# Module.net
KiCad netlist of a schematic drawn in Altium Designer
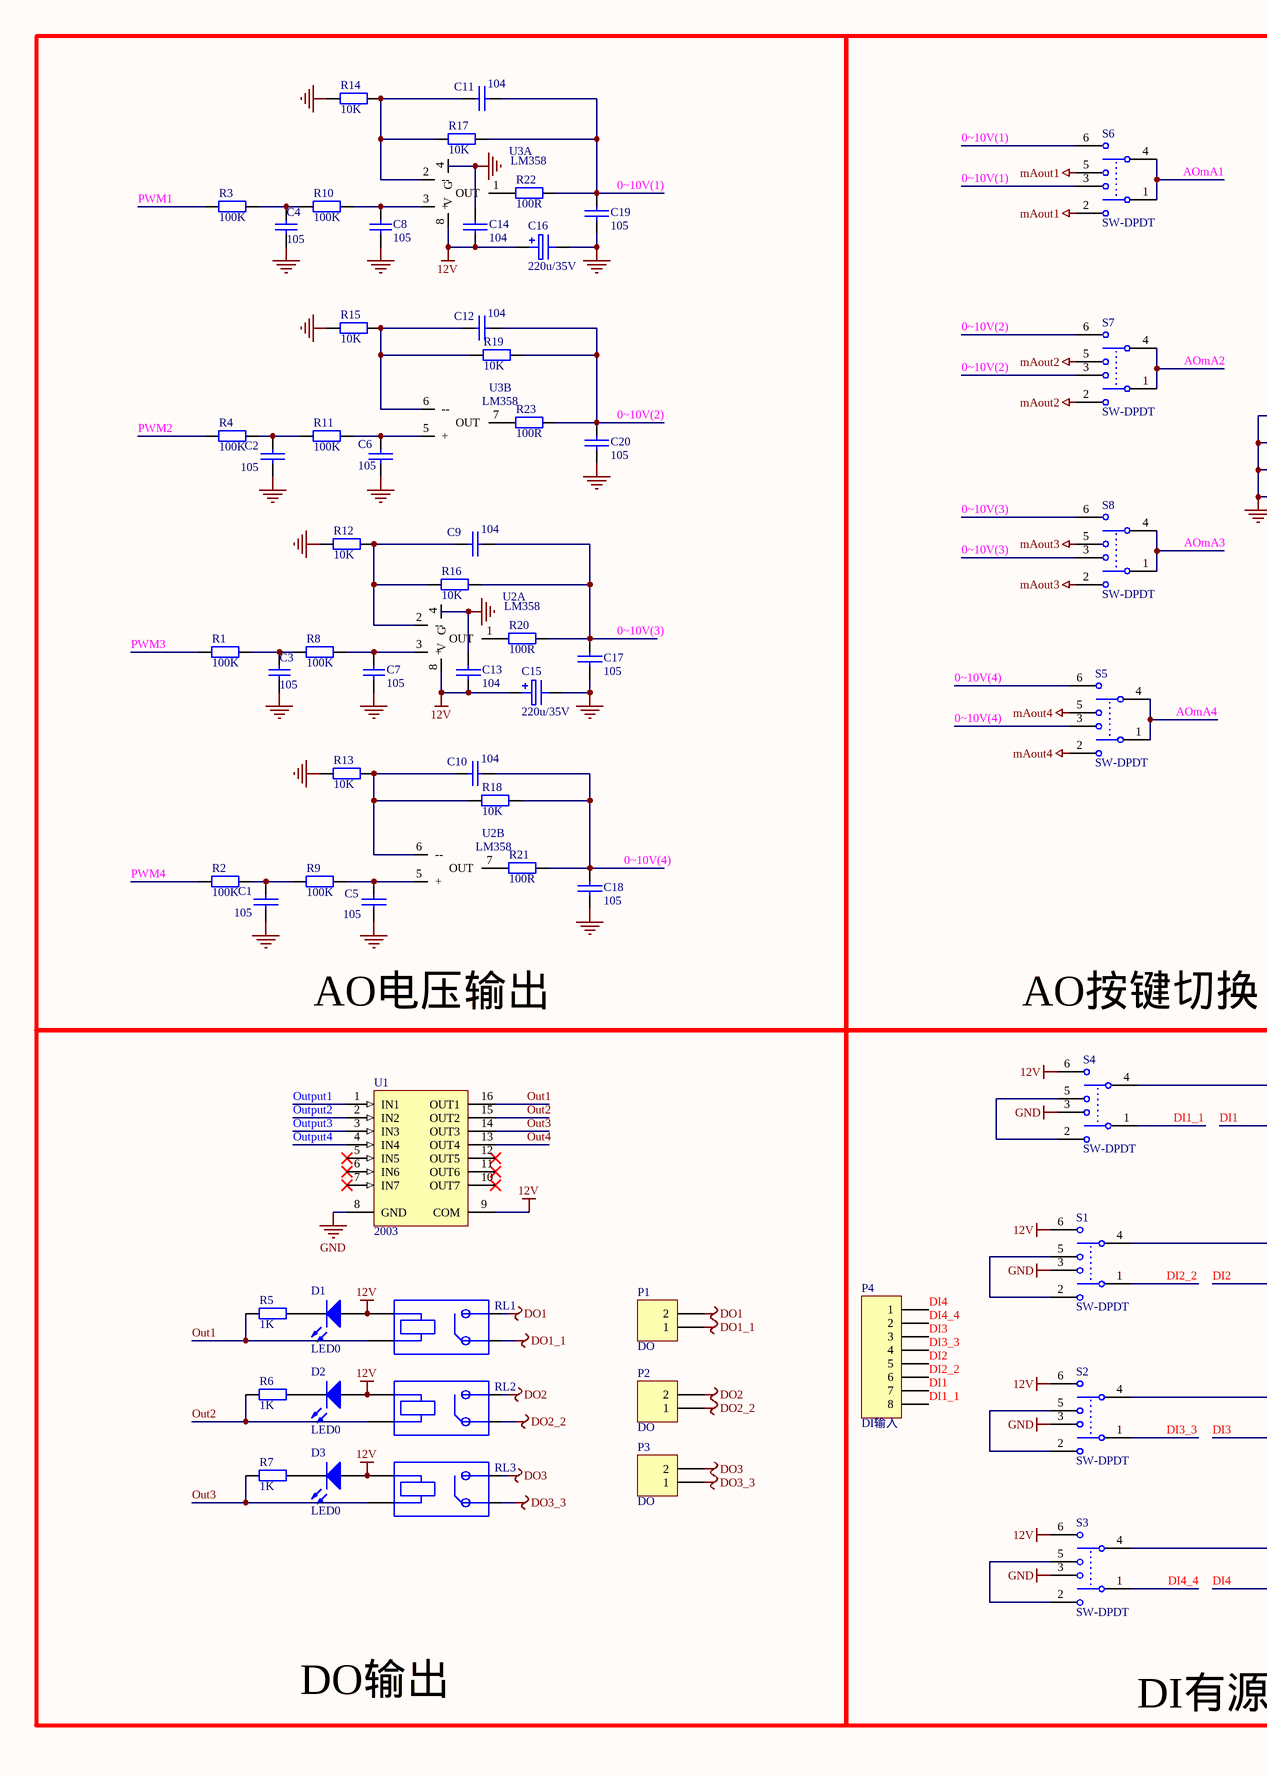
[diagram p0: Module.SchDoc, left]
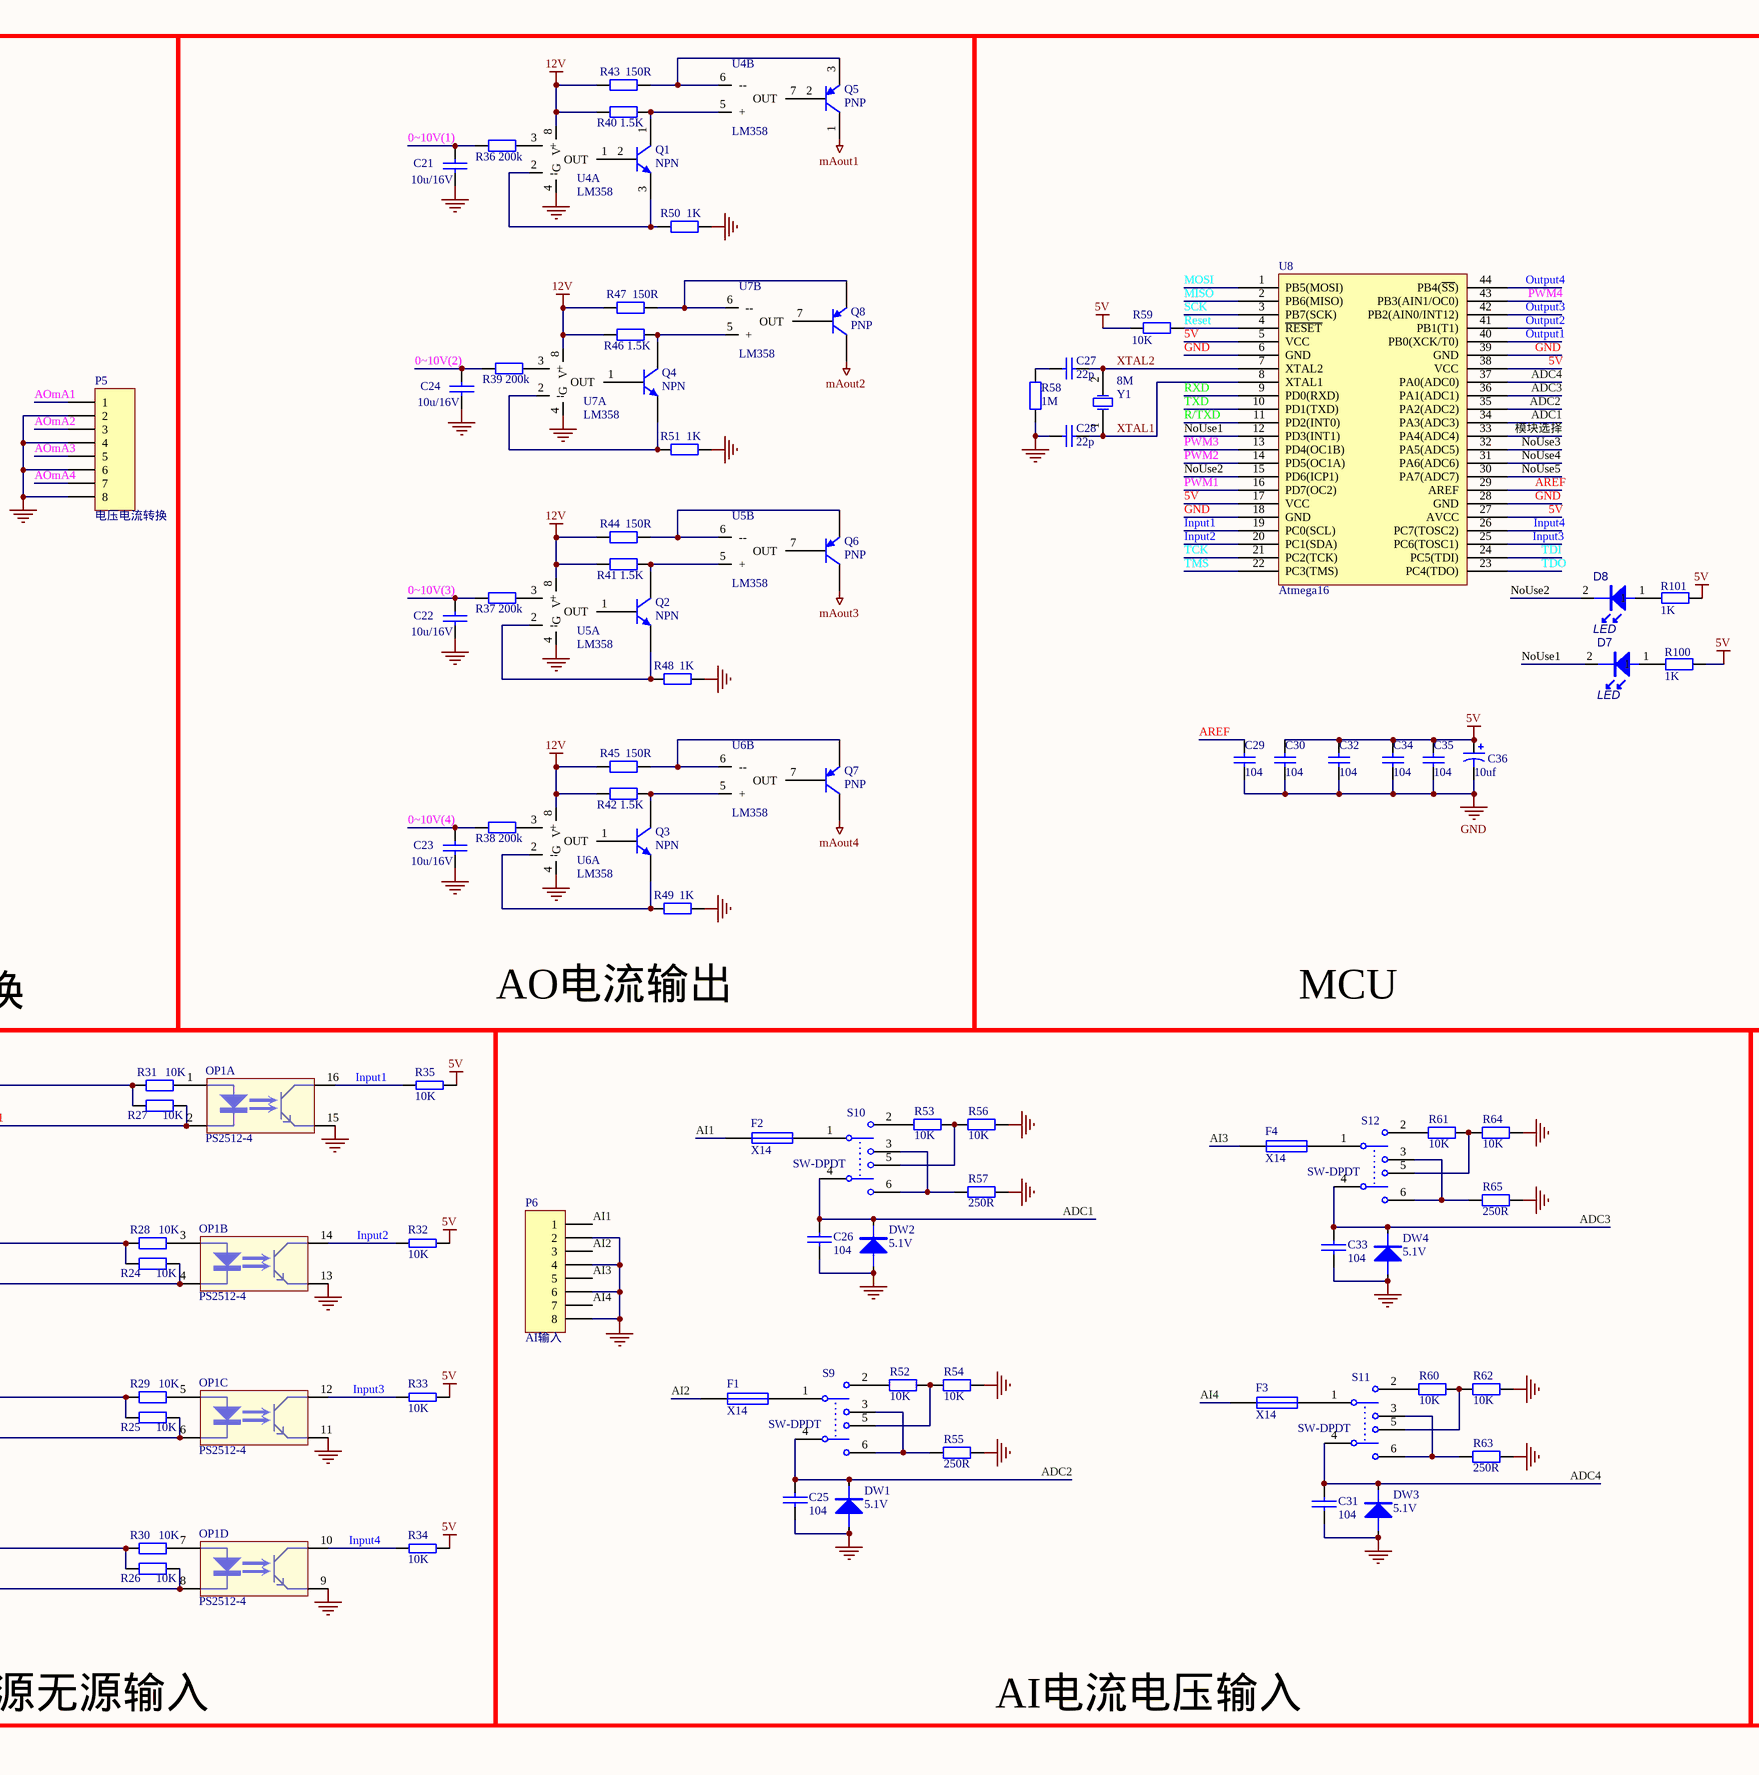
[diagram p1: Module.SchDoc, middle]
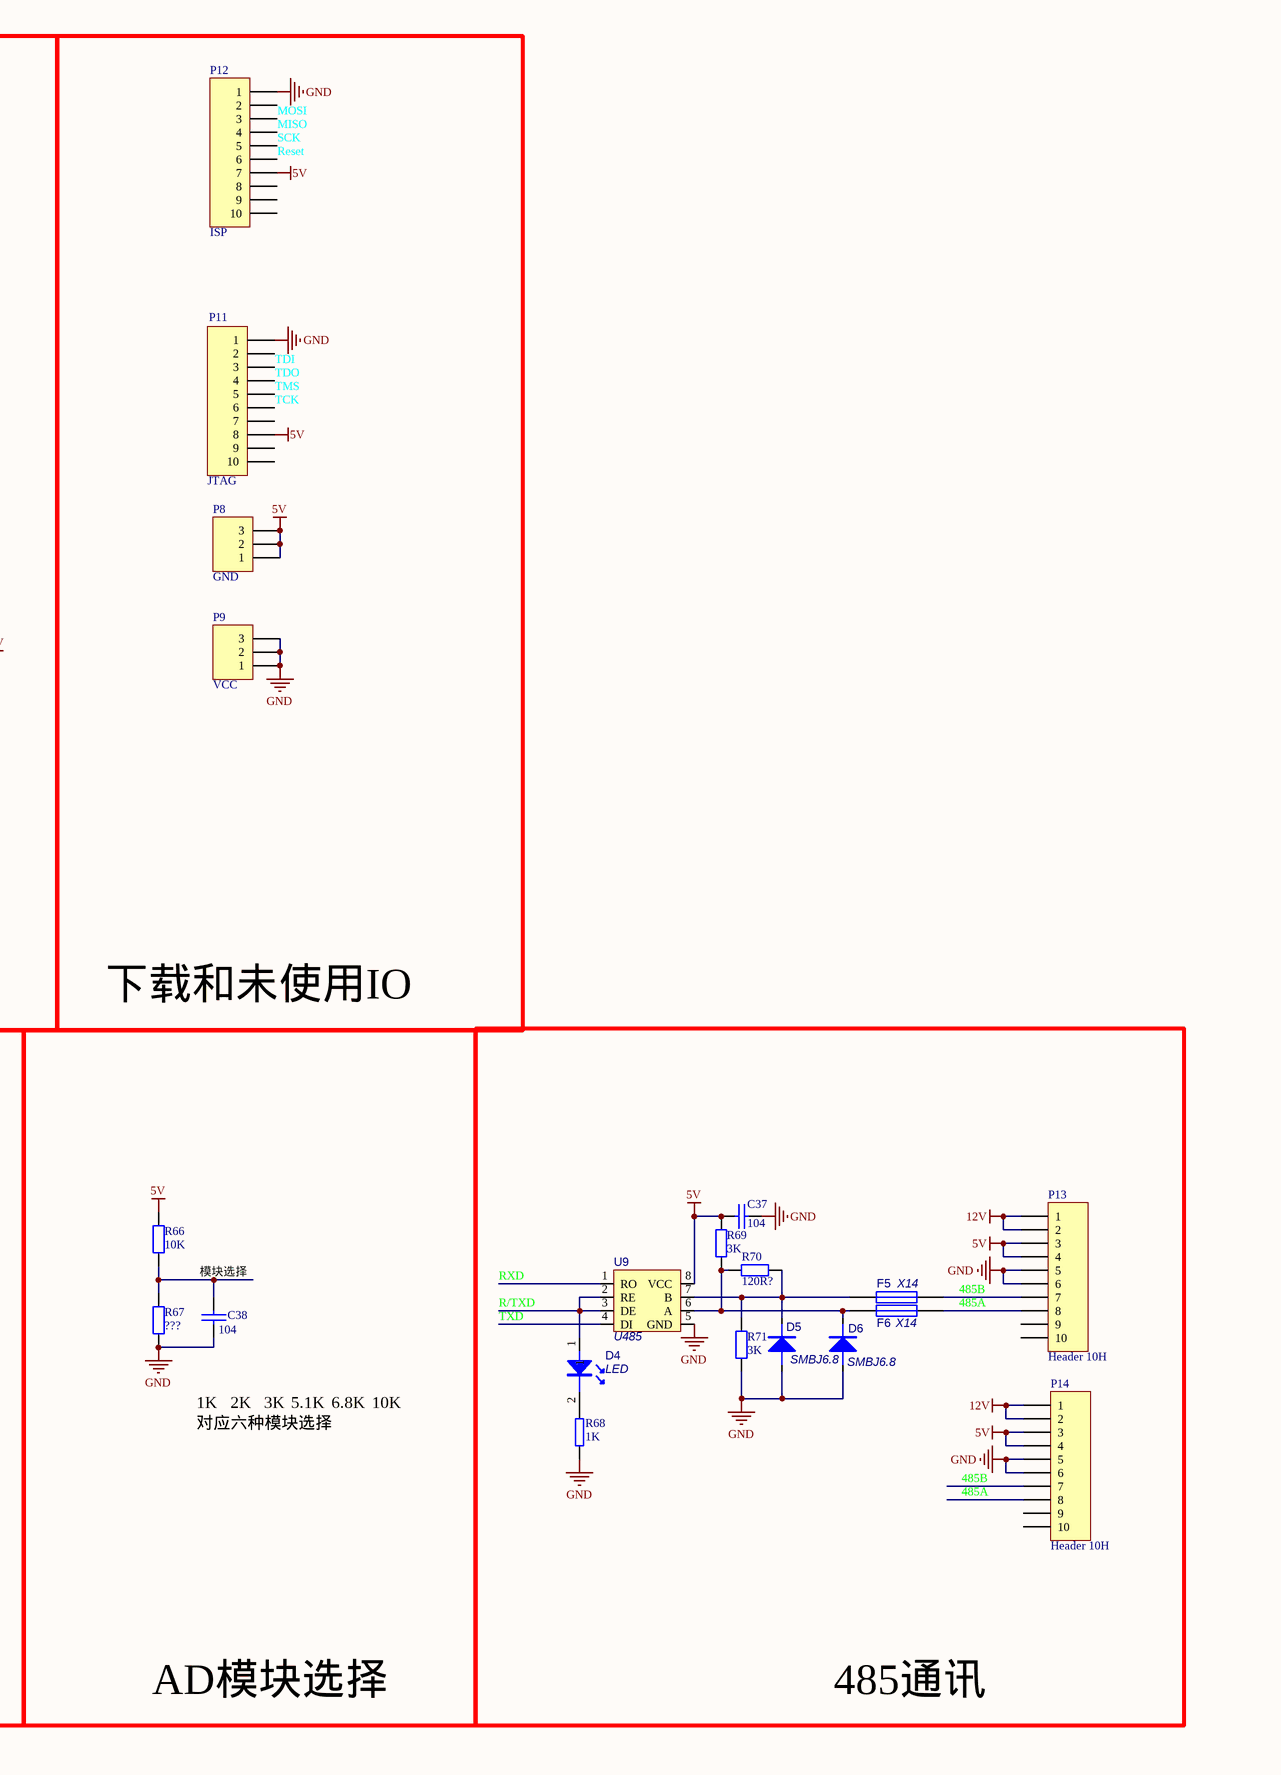
[diagram p2: Module.SchDoc, right]

(export (version "E")
  (design (tool "Eeschema 10.0.6"))
  (components
    (comp (ref "C1")
      (value "105")
      (footprint "C0805C")
      (description "Capacitor")
      (libsource (lib "*") (part "CAP"))
    )
    (comp (ref "C2")
      (value "105")
      (footprint "C0805C")
      (description "Capacitor")
      (libsource (lib "*") (part "CAP"))
    )
    (comp (ref "C3")
      (value "105")
      (footprint "c0805c")
      (description "Capacitor")
      (fields (field (name "PUBLISHER") "Altium Limited"))
      (libsource (lib "*") (part "Cap"))
    )
    (comp (ref "C4")
      (value "105")
      (footprint "c0805c")
      (description "Capacitor")
      (fields (field (name "PUBLISHER") "Altium Limited"))
      (libsource (lib "*") (part "Cap"))
    )
    (comp (ref "C5")
      (value "105")
      (footprint "C0805C")
      (description "Capacitor")
      (libsource (lib "*") (part "CAP"))
    )
    (comp (ref "C6")
      (value "105")
      (footprint "C0805C")
      (description "Capacitor")
      (libsource (lib "*") (part "CAP"))
    )
    (comp (ref "C7")
      (value "105")
      (footprint "c0805c")
      (description "Capacitor")
      (fields (field (name "PUBLISHER") "Altium Limited"))
      (libsource (lib "*") (part "Cap"))
    )
    (comp (ref "C8")
      (value "105")
      (footprint "c0805c")
      (description "Capacitor")
      (fields (field (name "PUBLISHER") "Altium Limited"))
      (libsource (lib "*") (part "Cap"))
    )
    (comp (ref "C9")
      (value "104")
      (footprint "C0805C")
      (description "Capacitor")
      (libsource (lib "*") (part "CAP"))
    )
    (comp (ref "C10")
      (value "104")
      (footprint "C0805C")
      (description "Capacitor")
      (libsource (lib "*") (part "CAP"))
    )
    (comp (ref "C11")
      (value "104")
      (footprint "C0805C")
      (description "Capacitor")
      (libsource (lib "*") (part "CAP"))
    )
    (comp (ref "C12")
      (value "104")
      (footprint "C0805C")
      (description "Capacitor")
      (libsource (lib "*") (part "CAP"))
    )
    (comp (ref "C13")
      (value "104")
      (footprint "C0805C")
      (description "Capacitor")
      (libsource (lib "*") (part "CAP"))
    )
    (comp (ref "C14")
      (value "104")
      (footprint "C0805C")
      (description "Capacitor")
      (libsource (lib "*") (part "CAP"))
    )
    (comp (ref "C15")
      (value "220u/35V")
      (footprint "E8MM")
      (description "Electrolytic Capacitor")
      (libsource (lib "*") (part "ELECTRO1"))
    )
    (comp (ref "C16")
      (value "220u/35V")
      (footprint "E8MM")
      (description "Electrolytic Capacitor")
      (libsource (lib "*") (part "ELECTRO1"))
    )
    (comp (ref "C17")
      (value "105")
      (footprint "C0805C")
      (description "Capacitor")
      (libsource (lib "*") (part "CAP"))
    )
    (comp (ref "C18")
      (value "105")
      (footprint "C0805C")
      (description "Capacitor")
      (libsource (lib "*") (part "CAP"))
    )
    (comp (ref "C19")
      (value "105")
      (footprint "C0805C")
      (description "Capacitor")
      (libsource (lib "*") (part "CAP"))
    )
    (comp (ref "C20")
      (value "105")
      (footprint "C0805C")
      (description "Capacitor")
      (libsource (lib "*") (part "CAP"))
    )
    (comp (ref "C21")
      (value "10u/16V")
      (footprint "1206")
      (description "Capacitor")
      (libsource (lib "*") (part "CAP"))
    )
    (comp (ref "C22")
      (value "10u/16V")
      (footprint "1206")
      (description "Capacitor")
      (libsource (lib "*") (part "CAP"))
    )
    (comp (ref "C23")
      (value "10u/16V")
      (footprint "1206")
      (description "Capacitor")
      (libsource (lib "*") (part "CAP"))
    )
    (comp (ref "C24")
      (value "10u/16V")
      (footprint "1206")
      (description "Capacitor")
      (libsource (lib "*") (part "CAP"))
    )
    (comp (ref "C25")
      (value "104")
      (footprint "C0805C")
      (description "Capacitor")
      (libsource (lib "*") (part "CAP"))
    )
    (comp (ref "C26")
      (value "104")
      (footprint "C0805C")
      (description "Capacitor")
      (libsource (lib "*") (part "CAP"))
    )
    (comp (ref "C27")
      (value "22p")
      (footprint "c0805c")
      (description "Capacitor")
      (fields (field (name "PUBLISHER") "Altium Limited"))
      (libsource (lib "*") (part "Cap"))
    )
    (comp (ref "C28")
      (value "22p")
      (footprint "c0805c")
      (description "Capacitor")
      (fields (field (name "PUBLISHER") "Altium Limited"))
      (libsource (lib "*") (part "Cap"))
    )
    (comp (ref "C29")
      (value "104")
      (footprint "c0805c")
      (description "Capacitor")
      (fields (field (name "PUBLISHER") "Altium Limited"))
      (libsource (lib "*") (part "Cap"))
    )
    (comp (ref "C30")
      (value "104")
      (footprint "c0805c")
      (description "Capacitor")
      (fields (field (name "PUBLISHER") "Altium Limited"))
      (libsource (lib "*") (part "Cap"))
    )
    (comp (ref "C31")
      (value "104")
      (footprint "C0805C")
      (description "Capacitor")
      (libsource (lib "*") (part "CAP"))
    )
    (comp (ref "C32")
      (value "104")
      (footprint "c0805c")
      (description "Capacitor")
      (fields (field (name "PUBLISHER") "Altium Limited"))
      (libsource (lib "*") (part "Cap"))
    )
    (comp (ref "C33")
      (value "104")
      (footprint "C0805C")
      (description "Capacitor")
      (libsource (lib "*") (part "CAP"))
    )
    (comp (ref "C34")
      (value "104")
      (footprint "c0805c")
      (description "Capacitor")
      (fields (field (name "PUBLISHER") "Altium Limited"))
      (libsource (lib "*") (part "Cap"))
    )
    (comp (ref "C35")
      (value "104")
      (footprint "c0805c")
      (description "Capacitor")
      (fields (field (name "PUBLISHER") "Altium Limited"))
      (libsource (lib "*") (part "Cap"))
    )
    (comp (ref "C36")
      (value "10uf")
      (footprint "E6.5MM")
      (description "Polarized Capacitor (Radial)")
      (fields (field (name "PUBLISHER") "Altium Limited"))
      (libsource (lib "PCB_Project1") (part "Cap Pol1"))
    )
    (comp (ref "C37")
      (value "104")
      (footprint "C0805C")
      (description "Capacitor")
      (libsource (lib "*") (part "CAP"))
    )
    (comp (ref "C38")
      (value "104")
      (footprint "C0805C")
      (description "Capacitor")
      (libsource (lib "*") (part "CAP"))
    )
    (comp (ref "D1")
      (value "LED0")
      (footprint "LED0805")
      (description "Typical INFRARED GaAs LED")
      (fields (field (name "PUBLISHER") "Altium Limited"))
      (libsource (lib "Miscellaneous Devices") (part "LED0"))
    )
    (comp (ref "D2")
      (value "LED0")
      (footprint "LED0805")
      (description "Typical INFRARED GaAs LED")
      (fields (field (name "PUBLISHER") "Altium Limited"))
      (libsource (lib "Miscellaneous Devices") (part "LED0"))
    )
    (comp (ref "D3")
      (value "LED0")
      (footprint "LED0805")
      (description "Typical INFRARED GaAs LED")
      (fields (field (name "PUBLISHER") "Altium Limited"))
      (libsource (lib "Miscellaneous Devices") (part "LED0"))
    )
    (comp (ref "D4") (value "LED") (footprint "LED0805") (libsource (lib "*") (part "LED")))
    (comp (ref "D5")
      (value "SMBJ6.8")
      (footprint "SMBJ_SMT")
      (description "Diode")
      (libsource (lib "*") (part "DIODE"))
    )
    (comp (ref "D6")
      (value "SMBJ6.8")
      (footprint "SMBJ_SMT")
      (description "Diode")
      (libsource (lib "*") (part "DIODE"))
    )
    (comp (ref "D7") (value "LED") (footprint "LED0805") (libsource (lib "*") (part "LED")))
    (comp (ref "D8") (value "LED") (footprint "LED0805") (libsource (lib "*") (part "LED")))
    (comp (ref "DW1")
      (value "5.1V")
      (footprint "1206AK")
      (description "Diode")
      (libsource (lib "*") (part "DIODE"))
    )
    (comp (ref "DW2")
      (value "5.1V")
      (footprint "1206AK")
      (description "Diode")
      (libsource (lib "*") (part "DIODE"))
    )
    (comp (ref "DW3")
      (value "5.1V")
      (footprint "1206AK")
      (description "Diode")
      (libsource (lib "*") (part "DIODE"))
    )
    (comp (ref "DW4")
      (value "5.1V")
      (footprint "1206AK")
      (description "Diode")
      (libsource (lib "*") (part "DIODE"))
    )
    (comp (ref "F1")
      (value "X14")
      (footprint "PPTC_SMT")
      (description "Fuse")
      (fields (field (name "PUBLISHER") "Altium Limited"))
      (libsource (lib "Miscellaneous Devices") (part "Fuse 1"))
    )
    (comp (ref "F2")
      (value "X14")
      (footprint "PPTC_SMT")
      (description "Fuse")
      (fields (field (name "PUBLISHER") "Altium Limited"))
      (libsource (lib "Miscellaneous Devices") (part "Fuse 1"))
    )
    (comp (ref "F3")
      (value "X14")
      (footprint "PPTC_SMT")
      (description "Fuse")
      (fields (field (name "PUBLISHER") "Altium Limited"))
      (libsource (lib "Miscellaneous Devices") (part "Fuse 1"))
    )
    (comp (ref "F4")
      (value "X14")
      (footprint "PPTC_SMT")
      (description "Fuse")
      (fields (field (name "PUBLISHER") "Altium Limited"))
      (libsource (lib "Miscellaneous Devices") (part "Fuse 1"))
    )
    (comp (ref "F5")
      (value "X14")
      (footprint "PPTC_SMT")
      (description "Fuse")
      (fields (field (name "PUBLISHER") "Altium Limited"))
      (libsource (lib "Miscellaneous Devices") (part "Fuse 1"))
    )
    (comp (ref "F6")
      (value "X14")
      (footprint "PPTC_SMT")
      (description "Fuse")
      (fields (field (name "PUBLISHER") "Altium Limited"))
      (libsource (lib "Miscellaneous Devices") (part "Fuse 1"))
    )
    (comp (ref "OP1") (value "PS2512-4") (footprint "SO_16") (libsource (lib "POLx") (part "PS2512-4")))
    (comp (ref "P1")
      (value "DO")
      (footprint "PL2Q")
      (description "Header, 2-Pin")
      (fields (field (name "PUBLISHER") "Altium Limited"))
      (libsource (lib "*") (part "Header 2"))
    )
    (comp (ref "P2")
      (value "DO")
      (footprint "PL2Q")
      (description "Header, 2-Pin")
      (fields (field (name "PUBLISHER") "Altium Limited"))
      (libsource (lib "*") (part "Header 2"))
    )
    (comp (ref "P3")
      (value "DO")
      (footprint "PL2Q")
      (description "Header, 2-Pin")
      (fields (field (name "PUBLISHER") "Altium Limited"))
      (libsource (lib "*") (part "Header 2"))
    )
    (comp (ref "P4")
      (value "DI输入")
      (footprint "8P _COM")
      (description "Header, 8-Pin")
      (fields (field (name "PUBLISHER") "Altium Limited"))
      (libsource (lib "") (part "Header 8_1"))
    )
    (comp (ref "P5")
      (value "电压电流转换")
      (footprint "8P _COM")
      (description "Header, 8-Pin")
      (fields (field (name "PUBLISHER") "Altium Limited"))
      (libsource (lib "Miscellaneous Connectors") (part "Header 8"))
    )
    (comp (ref "P6")
      (value "AI输入")
      (footprint "8P _COM")
      (description "Header, 8-Pin")
      (fields (field (name "PUBLISHER") "Altium Limited"))
      (libsource (lib "") (part "Header 8_1"))
    )
    (comp (ref "P8")
      (value "GND")
      (footprint "HDR1X3")
      (description "Header, 3-Pin")
      (fields (field (name "PUBLISHER") "Altium Limited"))
      (libsource (lib "Miscellaneous Connectors") (part "Header 3"))
    )
    (comp (ref "P9")
      (value "VCC")
      (footprint "HDR1X3")
      (description "Header, 3-Pin")
      (fields (field (name "PUBLISHER") "Altium Limited"))
      (libsource (lib "Miscellaneous Connectors") (part "Header 3"))
    )
    (comp (ref "P11")
      (value "JTAG")
      (footprint "FC10")
      (description "Header, 10-Pin, Right Angle")
      (fields (field (name "PUBLISHER") "Altium Limited"))
      (libsource (lib "") (part "Header 10H_1"))
    )
    (comp (ref "P12")
      (value "ISP")
      (footprint "FC10")
      (description "Header, 10-Pin, Right Angle")
      (fields (field (name "PUBLISHER") "Altium Limited"))
      (libsource (lib "") (part "Header 10H_1"))
    )
    (comp (ref "P13")
      (value "Header 10H")
      (footprint "FC10P_wan")
      (description "Header, 10-Pin, Right Angle")
      (fields (field (name "PUBLISHER") "Altium Limited"))
      (libsource (lib "Miscellaneous Connectors") (part "Header 10H"))
    )
    (comp (ref "P14")
      (value "Header 10H")
      (footprint "FC10P_wan")
      (description "Header, 10-Pin, Right Angle")
      (fields (field (name "PUBLISHER") "Altium Limited"))
      (libsource (lib "Miscellaneous Connectors") (part "Header 10H"))
    )
    (comp (ref "Q1")
      (value "NPN")
      (footprint "SOT_23")
      (description "NPN Bipolar Transistor")
      (fields (field (name "PUBLISHER") "Altium Limited"))
      (libsource (lib "") (part "NPN_1"))
    )
    (comp (ref "Q2")
      (value "NPN")
      (footprint "SOT_23")
      (description "NPN Bipolar Transistor")
      (fields (field (name "PUBLISHER") "Altium Limited"))
      (libsource (lib "Miscellaneous Devices") (part "NPN"))
    )
    (comp (ref "Q3")
      (value "NPN")
      (footprint "SOT_23")
      (description "NPN Bipolar Transistor")
      (fields (field (name "PUBLISHER") "Altium Limited"))
      (libsource (lib "Miscellaneous Devices") (part "NPN"))
    )
    (comp (ref "Q4")
      (value "NPN")
      (footprint "SOT_23")
      (description "NPN Bipolar Transistor")
      (fields (field (name "PUBLISHER") "Altium Limited"))
      (libsource (lib "Miscellaneous Devices") (part "NPN"))
    )
    (comp (ref "Q5")
      (value "PNP")
      (footprint "SOT_23")
      (description "PNP Bipolar Transistor")
      (fields (field (name "PUBLISHER") "Altium Limited"))
      (libsource (lib "") (part "PNP_1"))
    )
    (comp (ref "Q6")
      (value "PNP")
      (footprint "SOT_23")
      (description "PNP Bipolar Transistor")
      (fields (field (name "PUBLISHER") "Altium Limited"))
      (libsource (lib "Miscellaneous Devices") (part "PNP"))
    )
    (comp (ref "Q7")
      (value "PNP")
      (footprint "SOT_23")
      (description "PNP Bipolar Transistor")
      (fields (field (name "PUBLISHER") "Altium Limited"))
      (libsource (lib "Miscellaneous Devices") (part "PNP"))
    )
    (comp (ref "Q8")
      (value "PNP")
      (footprint "SOT_23")
      (description "PNP Bipolar Transistor")
      (fields (field (name "PUBLISHER") "Altium Limited"))
      (libsource (lib "Miscellaneous Devices") (part "PNP"))
    )
    (comp (ref "R1")
      (value "100K")
      (footprint "0805R")
      (description "Resistor")
      (fields (field (name "PUBLISHER") "Altium Limited"))
      (libsource (lib "Miscellaneous Devices") (part "res"))
    )
    (comp (ref "R2")
      (value "100K")
      (footprint "0805R")
      (description "Resistor")
      (fields (field (name "PUBLISHER") "Altium Limited"))
      (libsource (lib "Miscellaneous Devices") (part "res"))
    )
    (comp (ref "R3")
      (value "100K")
      (footprint "0805R")
      (description "Resistor")
      (fields (field (name "PUBLISHER") "Altium Limited"))
      (libsource (lib "Miscellaneous Devices") (part "res"))
    )
    (comp (ref "R4")
      (value "100K")
      (footprint "0805R")
      (description "Resistor")
      (fields (field (name "PUBLISHER") "Altium Limited"))
      (libsource (lib "Miscellaneous Devices") (part "res"))
    )
    (comp (ref "R5")
      (value "1K")
      (footprint "0805R")
      (description "Resistor")
      (fields (field (name "PUBLISHER") "Altium Limited"))
      (libsource (lib "Miscellaneous Devices") (part "res"))
    )
    (comp (ref "R6")
      (value "1K")
      (footprint "0805R")
      (description "Resistor")
      (fields (field (name "PUBLISHER") "Altium Limited"))
      (libsource (lib "Miscellaneous Devices") (part "res"))
    )
    (comp (ref "R7")
      (value "1K")
      (footprint "0805R")
      (description "Resistor")
      (fields (field (name "PUBLISHER") "Altium Limited"))
      (libsource (lib "Miscellaneous Devices") (part "res"))
    )
    (comp (ref "R8")
      (value "100K")
      (footprint "0805R")
      (description "Resistor")
      (fields (field (name "PUBLISHER") "Altium Limited"))
      (libsource (lib "Miscellaneous Devices") (part "res"))
    )
    (comp (ref "R9")
      (value "100K")
      (footprint "0805R")
      (description "Resistor")
      (fields (field (name "PUBLISHER") "Altium Limited"))
      (libsource (lib "Miscellaneous Devices") (part "res"))
    )
    (comp (ref "R10")
      (value "100K")
      (footprint "0805R")
      (description "Resistor")
      (fields (field (name "PUBLISHER") "Altium Limited"))
      (libsource (lib "Miscellaneous Devices") (part "res"))
    )
    (comp (ref "R11")
      (value "100K")
      (footprint "0805R")
      (description "Resistor")
      (fields (field (name "PUBLISHER") "Altium Limited"))
      (libsource (lib "Miscellaneous Devices") (part "res"))
    )
    (comp (ref "R12")
      (value "10K")
      (footprint "0805R")
      (description "Resistor")
      (fields (field (name "PUBLISHER") "Altium Limited"))
      (libsource (lib "Miscellaneous Devices") (part "res"))
    )
    (comp (ref "R13")
      (value "10K")
      (footprint "0805R")
      (description "Resistor")
      (fields (field (name "PUBLISHER") "Altium Limited"))
      (libsource (lib "Miscellaneous Devices") (part "res"))
    )
    (comp (ref "R14")
      (value "10K")
      (footprint "0805R")
      (description "Resistor")
      (fields (field (name "PUBLISHER") "Altium Limited"))
      (libsource (lib "Miscellaneous Devices") (part "res"))
    )
    (comp (ref "R15")
      (value "10K")
      (footprint "0805R")
      (description "Resistor")
      (fields (field (name "PUBLISHER") "Altium Limited"))
      (libsource (lib "Miscellaneous Devices") (part "res"))
    )
    (comp (ref "R16")
      (value "10K")
      (footprint "0805R")
      (description "Resistor")
      (fields (field (name "PUBLISHER") "Altium Limited"))
      (libsource (lib "Miscellaneous Devices") (part "res"))
    )
    (comp (ref "R17")
      (value "10K")
      (footprint "0805R")
      (description "Resistor")
      (fields (field (name "PUBLISHER") "Altium Limited"))
      (libsource (lib "Miscellaneous Devices") (part "res"))
    )
    (comp (ref "R18")
      (value "10K")
      (footprint "0805R")
      (description "Resistor")
      (fields (field (name "PUBLISHER") "Altium Limited"))
      (libsource (lib "Miscellaneous Devices") (part "res"))
    )
    (comp (ref "R19")
      (value "10K")
      (footprint "0805R")
      (description "Resistor")
      (fields (field (name "PUBLISHER") "Altium Limited"))
      (libsource (lib "Miscellaneous Devices") (part "res"))
    )
    (comp (ref "R20")
      (value "100R")
      (footprint "0805R")
      (description "Resistor")
      (fields (field (name "PUBLISHER") "Altium Limited"))
      (libsource (lib "Miscellaneous Devices") (part "res"))
    )
    (comp (ref "R21")
      (value "100R")
      (footprint "NDLib:0805R")
      (description "Resistor")
      (fields (field (name "PUBLISHER") "Altium Limited"))
      (libsource (lib "Miscellaneous Devices") (part "res"))
    )
    (comp (ref "R22")
      (value "100R")
      (footprint "0805R")
      (description "Resistor")
      (fields (field (name "PUBLISHER") "Altium Limited"))
      (libsource (lib "Miscellaneous Devices") (part "res"))
    )
    (comp (ref "R23")
      (value "100R")
      (footprint "0805R")
      (description "Resistor")
      (fields (field (name "PUBLISHER") "Altium Limited"))
      (libsource (lib "Miscellaneous Devices") (part "res"))
    )
    (comp (ref "R24")
      (value "10K")
      (footprint "0805R")
      (description "Resistor")
      (fields (field (name "PUBLISHER") "Altium Limited"))
      (libsource (lib "") (part "res_2"))
    )
    (comp (ref "R25")
      (value "10K")
      (footprint "0805R")
      (description "Resistor")
      (fields (field (name "PUBLISHER") "Altium Limited"))
      (libsource (lib "") (part "res_2"))
    )
    (comp (ref "R26")
      (value "10K")
      (footprint "0805R")
      (description "Resistor")
      (fields (field (name "PUBLISHER") "Altium Limited"))
      (libsource (lib "") (part "res_2"))
    )
    (comp (ref "R27")
      (value "10K")
      (footprint "0805R")
      (description "Resistor")
      (fields (field (name "PUBLISHER") "Altium Limited"))
      (libsource (lib "") (part "res_2"))
    )
    (comp (ref "R28")
      (value "10K")
      (footprint "0805R")
      (description "Resistor")
      (fields (field (name "PUBLISHER") "Altium Limited"))
      (libsource (lib "") (part "res_2"))
    )
    (comp (ref "R29")
      (value "10K")
      (footprint "0805R")
      (description "Resistor")
      (fields (field (name "PUBLISHER") "Altium Limited"))
      (libsource (lib "") (part "res_2"))
    )
    (comp (ref "R30")
      (value "10K")
      (footprint "0805R")
      (description "Resistor")
      (fields (field (name "PUBLISHER") "Altium Limited"))
      (libsource (lib "") (part "res_2"))
    )
    (comp (ref "R31")
      (value "10K")
      (footprint "0805R")
      (description "Resistor")
      (fields (field (name "PUBLISHER") "Altium Limited"))
      (libsource (lib "") (part "res_2"))
    )
    (comp (ref "R32") (value "10K") (footprint "0805R") (libsource (lib "*") (part "res")))
    (comp (ref "R33") (value "10K") (footprint "0805R") (libsource (lib "*") (part "res")))
    (comp (ref "R34") (value "10K") (footprint "0805R") (libsource (lib "*") (part "res")))
    (comp (ref "R35") (value "10K") (footprint "0805R") (libsource (lib "*") (part "res")))
    (comp (ref "R36")
      (value "200k")
      (footprint "0805R")
      (description "Resistor")
      (fields (field (name "PUBLISHER") "Altium Limited"))
      (libsource (lib "Miscellaneous Devices") (part "res"))
    )
    (comp (ref "R37")
      (value "200k")
      (footprint "0805R")
      (description "Resistor")
      (fields (field (name "PUBLISHER") "Altium Limited"))
      (libsource (lib "Miscellaneous Devices") (part "res"))
    )
    (comp (ref "R38")
      (value "200k")
      (footprint "0805R")
      (description "Resistor")
      (fields (field (name "PUBLISHER") "Altium Limited"))
      (libsource (lib "Miscellaneous Devices") (part "res"))
    )
    (comp (ref "R39")
      (value "200k")
      (footprint "0805R")
      (description "Resistor")
      (fields (field (name "PUBLISHER") "Altium Limited"))
      (libsource (lib "Miscellaneous Devices") (part "res"))
    )
    (comp (ref "R40")
      (value "1.5K")
      (footprint "0805R")
      (description "Resistor")
      (fields (field (name "PUBLISHER") "Altium Limited"))
      (libsource (lib "Miscellaneous Devices") (part "res"))
    )
    (comp (ref "R41")
      (value "1.5K")
      (footprint "0805R")
      (description "Resistor")
      (fields (field (name "PUBLISHER") "Altium Limited"))
      (libsource (lib "Miscellaneous Devices") (part "res"))
    )
    (comp (ref "R42")
      (value "1.5K")
      (footprint "0805R")
      (description "Resistor")
      (fields (field (name "PUBLISHER") "Altium Limited"))
      (libsource (lib "Miscellaneous Devices") (part "res"))
    )
    (comp (ref "R43")
      (value "150R")
      (footprint "0805R")
      (description "Resistor")
      (fields (field (name "PUBLISHER") "Altium Limited"))
      (libsource (lib "Miscellaneous Devices") (part "res"))
    )
    (comp (ref "R44")
      (value "150R")
      (footprint "0805R")
      (description "Resistor")
      (fields (field (name "PUBLISHER") "Altium Limited"))
      (libsource (lib "Miscellaneous Devices") (part "res"))
    )
    (comp (ref "R45")
      (value "150R")
      (footprint "0805R")
      (description "Resistor")
      (fields (field (name "PUBLISHER") "Altium Limited"))
      (libsource (lib "Miscellaneous Devices") (part "res"))
    )
    (comp (ref "R46")
      (value "1.5K")
      (footprint "0805R")
      (description "Resistor")
      (fields (field (name "PUBLISHER") "Altium Limited"))
      (libsource (lib "Miscellaneous Devices") (part "res"))
    )
    (comp (ref "R47")
      (value "150R")
      (footprint "0805R")
      (description "Resistor")
      (fields (field (name "PUBLISHER") "Altium Limited"))
      (libsource (lib "Miscellaneous Devices") (part "res"))
    )
    (comp (ref "R48")
      (value "1K")
      (footprint "0805R")
      (description "Resistor")
      (fields (field (name "PUBLISHER") "Altium Limited"))
      (libsource (lib "Miscellaneous Devices") (part "res"))
    )
    (comp (ref "R49")
      (value "1K")
      (footprint "0805R")
      (description "Resistor")
      (fields (field (name "PUBLISHER") "Altium Limited"))
      (libsource (lib "Miscellaneous Devices") (part "res"))
    )
    (comp (ref "R50")
      (value "1K")
      (footprint "0805R")
      (description "Resistor")
      (fields (field (name "PUBLISHER") "Altium Limited"))
      (libsource (lib "Miscellaneous Devices") (part "res"))
    )
    (comp (ref "R51")
      (value "1K")
      (footprint "0805R")
      (description "Resistor")
      (fields (field (name "PUBLISHER") "Altium Limited"))
      (libsource (lib "Miscellaneous Devices") (part "res"))
    )
    (comp (ref "R52")
      (value "10K")
      (footprint "0805R")
      (description "Resistor")
      (fields (field (name "PUBLISHER") "Altium Limited"))
      (libsource (lib "") (part "res_2"))
    )
    (comp (ref "R53")
      (value "10K")
      (footprint "0805R")
      (description "Resistor")
      (fields (field (name "PUBLISHER") "Altium Limited"))
      (libsource (lib "") (part "res_2"))
    )
    (comp (ref "R54")
      (value "10K")
      (footprint "0805R")
      (description "Resistor")
      (fields (field (name "PUBLISHER") "Altium Limited"))
      (libsource (lib "") (part "res_2"))
    )
    (comp (ref "R55")
      (value "250R")
      (footprint "0805R")
      (description "Resistor")
      (fields (field (name "PUBLISHER") "Altium Limited"))
      (libsource (lib "") (part "res_2"))
    )
    (comp (ref "R56")
      (value "10K")
      (footprint "0805R")
      (description "Resistor")
      (fields (field (name "PUBLISHER") "Altium Limited"))
      (libsource (lib "") (part "res_2"))
    )
    (comp (ref "R57")
      (value "250R")
      (footprint "0805R")
      (description "Resistor")
      (fields (field (name "PUBLISHER") "Altium Limited"))
      (libsource (lib "") (part "res_2"))
    )
    (comp (ref "R58")
      (value "1M")
      (footprint "0805R")
      (description "Resistor")
      (fields (field (name "PUBLISHER") "Altium Limited"))
      (libsource (lib "") (part "res_3"))
    )
    (comp (ref "R59")
      (value "10K")
      (footprint "0805R")
      (description "Resistor")
      (fields (field (name "PUBLISHER") "Altium Limited"))
      (libsource (lib "Miscellaneous Devices") (part "res"))
    )
    (comp (ref "R60")
      (value "10K")
      (footprint "0805R")
      (description "Resistor")
      (fields (field (name "PUBLISHER") "Altium Limited"))
      (libsource (lib "") (part "res_2"))
    )
    (comp (ref "R61")
      (value "10K")
      (footprint "0805R")
      (description "Resistor")
      (fields (field (name "PUBLISHER") "Altium Limited"))
      (libsource (lib "") (part "res_2"))
    )
    (comp (ref "R62")
      (value "10K")
      (footprint "0805R")
      (description "Resistor")
      (fields (field (name "PUBLISHER") "Altium Limited"))
      (libsource (lib "") (part "res_2"))
    )
    (comp (ref "R63")
      (value "250R")
      (footprint "0805R")
      (description "Resistor")
      (fields (field (name "PUBLISHER") "Altium Limited"))
      (libsource (lib "") (part "res_2"))
    )
    (comp (ref "R64")
      (value "10K")
      (footprint "0805R")
      (description "Resistor")
      (fields (field (name "PUBLISHER") "Altium Limited"))
      (libsource (lib "") (part "res_2"))
    )
    (comp (ref "R65")
      (value "250R")
      (footprint "0805R")
      (description "Resistor")
      (fields (field (name "PUBLISHER") "Altium Limited"))
      (libsource (lib "") (part "res_2"))
    )
    (comp (ref "R66")
      (value "10K")
      (footprint "0805R")
      (description "Resistor")
      (fields (field (name "PUBLISHER") "Altium Limited"))
      (libsource (lib "") (part "res_1"))
    )
    (comp (ref "R67")
      (value "???")
      (footprint "0805R")
      (description "Resistor")
      (fields (field (name "PUBLISHER") "Altium Limited"))
      (libsource (lib "") (part "res_1"))
    )
    (comp (ref "R68") (value "1K") (footprint "0805R") (libsource (lib "*") (part "res")))
    (comp (ref "R69")
      (value "3K")
      (footprint "0805R")
      (description "Resistor")
      (fields (field (name "PUBLISHER") "Altium Limited"))
      (libsource (lib "") (part "res_1"))
    )
    (comp (ref "R70")
      (value "120R?")
      (footprint "0805R")
      (description "Resistor")
      (fields (field (name "PUBLISHER") "Altium Limited"))
      (libsource (lib "") (part "res_2"))
    )
    (comp (ref "R71")
      (value "3K")
      (footprint "0805R")
      (description "Resistor")
      (fields (field (name "PUBLISHER") "Altium Limited"))
      (libsource (lib "") (part "res_1"))
    )
    (comp (ref "R100")
      (value "1K")
      (footprint "0805R")
      (description "Resistor")
      (fields (field (name "PUBLISHER") "Altium Limited"))
      (libsource (lib "Miscellaneous Devices") (part "res"))
    )
    (comp (ref "R101")
      (value "1K")
      (footprint "0805R")
      (description "Resistor")
      (fields (field (name "PUBLISHER") "Altium Limited"))
      (libsource (lib "Miscellaneous Devices") (part "res"))
    )
    (comp (ref "RL1") (value "~") (footprint "HF32A4") (libsource (lib "*") (part "RELAY")))
    (comp (ref "RL2") (value "~") (footprint "HF32A4") (libsource (lib "*") (part "RELAY")))
    (comp (ref "RL3") (value "~") (footprint "HF32A4") (libsource (lib "*") (part "RELAY")))
    (comp (ref "S1")
      (value "SW-DPDT")
      (footprint "button")
      (description "Double-Pole, Double-Throw Switch")
      (fields (field (name "PUBLISHER") "Altium Limited"))
      (libsource (lib "Miscellaneous Devices") (part "SW-DPDT"))
    )
    (comp (ref "S2")
      (value "SW-DPDT")
      (footprint "button")
      (description "Double-Pole, Double-Throw Switch")
      (fields (field (name "PUBLISHER") "Altium Limited"))
      (libsource (lib "Miscellaneous Devices") (part "SW-DPDT"))
    )
    (comp (ref "S3")
      (value "SW-DPDT")
      (footprint "button")
      (description "Double-Pole, Double-Throw Switch")
      (fields (field (name "PUBLISHER") "Altium Limited"))
      (libsource (lib "Miscellaneous Devices") (part "SW-DPDT"))
    )
    (comp (ref "S4")
      (value "SW-DPDT")
      (footprint "button")
      (description "Double-Pole, Double-Throw Switch")
      (fields (field (name "PUBLISHER") "Altium Limited"))
      (libsource (lib "Miscellaneous Devices") (part "SW-DPDT"))
    )
    (comp (ref "S5")
      (value "SW-DPDT")
      (footprint "button")
      (description "Double-Pole, Double-Throw Switch")
      (fields (field (name "PUBLISHER") "Altium Limited"))
      (libsource (lib "Miscellaneous Devices") (part "SW-DPDT"))
    )
    (comp (ref "S6")
      (value "SW-DPDT")
      (footprint "button")
      (description "Double-Pole, Double-Throw Switch")
      (fields (field (name "PUBLISHER") "Altium Limited"))
      (libsource (lib "Miscellaneous Devices") (part "SW-DPDT"))
    )
    (comp (ref "S7")
      (value "SW-DPDT")
      (footprint "button")
      (description "Double-Pole, Double-Throw Switch")
      (fields (field (name "PUBLISHER") "Altium Limited"))
      (libsource (lib "Miscellaneous Devices") (part "SW-DPDT"))
    )
    (comp (ref "S8")
      (value "SW-DPDT")
      (footprint "button")
      (description "Double-Pole, Double-Throw Switch")
      (fields (field (name "PUBLISHER") "Altium Limited"))
      (libsource (lib "Miscellaneous Devices") (part "SW-DPDT"))
    )
    (comp (ref "S9")
      (value "SW-DPDT")
      (footprint "button")
      (description "Double-Pole, Double-Throw Switch")
      (fields (field (name "PUBLISHER") "Altium Limited"))
      (libsource (lib "Miscellaneous Devices") (part "SW-DPDT"))
    )
    (comp (ref "S10")
      (value "SW-DPDT")
      (footprint "button")
      (description "Double-Pole, Double-Throw Switch")
      (fields (field (name "PUBLISHER") "Altium Limited"))
      (libsource (lib "Miscellaneous Devices") (part "SW-DPDT"))
    )
    (comp (ref "S11")
      (value "SW-DPDT")
      (footprint "button")
      (description "Double-Pole, Double-Throw Switch")
      (fields (field (name "PUBLISHER") "Altium Limited"))
      (libsource (lib "Miscellaneous Devices") (part "SW-DPDT"))
    )
    (comp (ref "S12")
      (value "SW-DPDT")
      (footprint "button")
      (description "Double-Pole, Double-Throw Switch")
      (fields (field (name "PUBLISHER") "Altium Limited"))
      (libsource (lib "Miscellaneous Devices") (part "SW-DPDT"))
    )
    (comp (ref "U1")
      (value "2003")
      (footprint "SO_16")
      (description "High-Voltage, High-Current Darlington Array")
      (fields (field (name "PUBLISHER") "*"))
      (libsource (lib "POLx") (part "ULN2003A"))
    )
    (comp (ref "U2") (value "LM358") (footprint "SOP-08") (libsource (lib "*") (part "LM358")))
    (comp (ref "U3") (value "LM358") (footprint "SOP-08") (libsource (lib "*") (part "LM358")))
    (comp (ref "U4") (value "LM358") (footprint "SOP-08") (libsource (lib "*") (part "LM358")))
    (comp (ref "U5") (value "LM358") (footprint "SOP-08") (libsource (lib "*") (part "LM358")))
    (comp (ref "U6") (value "LM358") (footprint "SOP-08") (libsource (lib "*") (part "LM358")))
    (comp (ref "U7") (value "LM358") (footprint "SOP-08") (libsource (lib "*") (part "LM358")))
    (comp (ref "U8")
      (value "Atmega16")
      (footprint "QFP44")
      (libsource (lib "CL_FS_A(V1.0)") (part "Atmega16"))
    )
    (comp (ref "U9") (value "U485") (footprint "SOP8") (libsource (lib "POL485") (part "U485")))
    (comp (ref "Y1")
      (value "8M")
      (footprint "XTAL-M")
      (description "Crystal Oscillator")
      (fields (field (name "PUBLISHER") "Altium Limited"))
      (libsource (lib "*") (part "XTAL"))
    )
  )
  (nets
    (net (code "1") (name "/0~10V(1)") (class "Default")
      (node (ref "C11") (pin "2") (pinfunction "2_2") (pintype "passive"))
      (node (ref "C19") (pin "1") (pinfunction "1_1") (pintype "passive"))
      (node (ref "C21") (pin "1") (pinfunction "1_1") (pintype "passive"))
      (node (ref "R17") (pin "1") (pinfunction "1_1") (pintype "passive"))
      (node (ref "R22") (pin "1") (pinfunction "1_1") (pintype "passive"))
      (node (ref "R36") (pin "2") (pinfunction "2_2") (pintype "passive"))
      (node (ref "S6") (pin "3") (pinfunction "3_3") (pintype "passive"))
      (node (ref "S6") (pin "6") (pinfunction "6_6") (pintype "passive"))
    )
    (net (code "2") (name "/0~10V(2)") (class "Default")
      (node (ref "C12") (pin "2") (pinfunction "2_2") (pintype "passive"))
      (node (ref "C20") (pin "1") (pinfunction "1_1") (pintype "passive"))
      (node (ref "C24") (pin "1") (pinfunction "1_1") (pintype "passive"))
      (node (ref "R19") (pin "1") (pinfunction "1_1") (pintype "passive"))
      (node (ref "R23") (pin "1") (pinfunction "1_1") (pintype "passive"))
      (node (ref "R39") (pin "2") (pinfunction "2_2") (pintype "passive"))
      (node (ref "S7") (pin "3") (pinfunction "3_3") (pintype "passive"))
      (node (ref "S7") (pin "6") (pinfunction "6_6") (pintype "passive"))
    )
    (net (code "3") (name "/0~10V(3)") (class "Default")
      (node (ref "C17") (pin "1") (pinfunction "1_1") (pintype "passive"))
      (node (ref "C22") (pin "1") (pinfunction "1_1") (pintype "passive"))
      (node (ref "C9") (pin "2") (pinfunction "2_2") (pintype "passive"))
      (node (ref "R16") (pin "1") (pinfunction "1_1") (pintype "passive"))
      (node (ref "R20") (pin "1") (pinfunction "1_1") (pintype "passive"))
      (node (ref "R37") (pin "2") (pinfunction "2_2") (pintype "passive"))
      (node (ref "S8") (pin "3") (pinfunction "3_3") (pintype "passive"))
      (node (ref "S8") (pin "6") (pinfunction "6_6") (pintype "passive"))
    )
    (net (code "4") (name "/0~10V(4)") (class "Default")
      (node (ref "C10") (pin "2") (pinfunction "2_2") (pintype "passive"))
      (node (ref "C18") (pin "1") (pinfunction "1_1") (pintype "passive"))
      (node (ref "C23") (pin "1") (pinfunction "1_1") (pintype "passive"))
      (node (ref "R18") (pin "1") (pinfunction "1_1") (pintype "passive"))
      (node (ref "R21") (pin "1") (pinfunction "1_1") (pintype "passive"))
      (node (ref "R38") (pin "2") (pinfunction "2_2") (pintype "passive"))
      (node (ref "S5") (pin "3") (pinfunction "3_3") (pintype "passive"))
      (node (ref "S5") (pin "6") (pinfunction "6_6") (pintype "passive"))
    )
    (net (code "5") (name "/485A") (class "Default")
      (node (ref "F6") (pin "1") (pinfunction "1_1") (pintype "passive"))
      (node (ref "P13") (pin "8") (pinfunction "8_8") (pintype "passive"))
      (node (ref "P14") (pin "8") (pinfunction "8_8") (pintype "passive"))
    )
    (net (code "6") (name "/485B") (class "Default")
      (node (ref "F5") (pin "1") (pinfunction "1_1") (pintype "passive"))
      (node (ref "P13") (pin "7") (pinfunction "7_7") (pintype "passive"))
      (node (ref "P14") (pin "7") (pinfunction "7_7") (pintype "passive"))
    )
    (net (code "7") (name "/ADC1") (class "Default")
      (node (ref "C26") (pin "1") (pinfunction "1_1") (pintype "passive"))
      (node (ref "DW2") (pin "K") (pinfunction "K_K") (pintype "passive"))
      (node (ref "S10") (pin "4") (pinfunction "4_4") (pintype "passive"))
      (node (ref "U8") (pin "34") (pinfunction "PA3(ADC3)_34") (pintype "passive"))
    )
    (net (code "8") (name "/ADC2") (class "Default")
      (node (ref "C25") (pin "1") (pinfunction "1_1") (pintype "passive"))
      (node (ref "DW1") (pin "K") (pinfunction "K_K") (pintype "passive"))
      (node (ref "S9") (pin "4") (pinfunction "4_4") (pintype "passive"))
      (node (ref "U8") (pin "35") (pinfunction "PA2(ADC2)_35") (pintype "passive"))
    )
    (net (code "9") (name "/ADC3") (class "Default")
      (node (ref "C33") (pin "1") (pinfunction "1_1") (pintype "passive"))
      (node (ref "DW4") (pin "K") (pinfunction "K_K") (pintype "passive"))
      (node (ref "S12") (pin "4") (pinfunction "4_4") (pintype "passive"))
      (node (ref "U8") (pin "36") (pinfunction "PA1(ADC1)_36") (pintype "passive"))
    )
    (net (code "10") (name "/ADC4") (class "Default")
      (node (ref "C31") (pin "1") (pinfunction "1_1") (pintype "passive"))
      (node (ref "DW3") (pin "K") (pinfunction "K_K") (pintype "passive"))
      (node (ref "S11") (pin "4") (pinfunction "4_4") (pintype "passive"))
      (node (ref "U8") (pin "37") (pinfunction "PA0(ADC0)_37") (pintype "passive"))
    )
    (net (code "11") (name "/AI1") (class "Default")
      (node (ref "F2") (pin "1") (pinfunction "1_1") (pintype "passive"))
      (node (ref "P6") (pin "1") (pinfunction "1_1") (pintype "passive"))
    )
    (net (code "12") (name "/AI2") (class "Default")
      (node (ref "F1") (pin "1") (pinfunction "1_1") (pintype "passive"))
      (node (ref "P6") (pin "3") (pinfunction "3_3") (pintype "passive"))
    )
    (net (code "13") (name "/AI3") (class "Default")
      (node (ref "F4") (pin "1") (pinfunction "1_1") (pintype "passive"))
      (node (ref "P6") (pin "5") (pinfunction "5_5") (pintype "passive"))
    )
    (net (code "14") (name "/AI4") (class "Default")
      (node (ref "F3") (pin "1") (pinfunction "1_1") (pintype "passive"))
      (node (ref "P6") (pin "7") (pinfunction "7_7") (pintype "passive"))
    )
    (net (code "15") (name "/AOmA1") (class "Default")
      (node (ref "P5") (pin "1") (pinfunction "1_1") (pintype "passive"))
      (node (ref "S6") (pin "1") (pinfunction "1_1") (pintype "passive"))
      (node (ref "S6") (pin "4") (pinfunction "4_4") (pintype "passive"))
    )
    (net (code "16") (name "/AOmA2") (class "Default")
      (node (ref "P5") (pin "3") (pinfunction "3_3") (pintype "passive"))
      (node (ref "S7") (pin "1") (pinfunction "1_1") (pintype "passive"))
      (node (ref "S7") (pin "4") (pinfunction "4_4") (pintype "passive"))
    )
    (net (code "17") (name "/AOmA3") (class "Default")
      (node (ref "P5") (pin "5") (pinfunction "5_5") (pintype "passive"))
      (node (ref "S8") (pin "1") (pinfunction "1_1") (pintype "passive"))
      (node (ref "S8") (pin "4") (pinfunction "4_4") (pintype "passive"))
    )
    (net (code "18") (name "/AOmA4") (class "Default")
      (node (ref "P5") (pin "7") (pinfunction "7_7") (pintype "passive"))
      (node (ref "S5") (pin "1") (pinfunction "1_1") (pintype "passive"))
      (node (ref "S5") (pin "4") (pinfunction "4_4") (pintype "passive"))
    )
    (net (code "19") (name "/AREF") (class "Default")
      (node (ref "C29") (pin "2") (pinfunction "2_2") (pintype "passive"))
      (node (ref "U8") (pin "29") (pinfunction "AREF_29") (pintype "passive"))
    )
    (net (code "20") (name "/DI1") (class "Default")
      (node (ref "OP1") (pin "2") (pinfunction "2_2") (pintype "passive"))
      (node (ref "P4") (pin "7") (pinfunction "7_7") (pintype "passive"))
      (node (ref "R27") (pin "2") (pinfunction "2_2") (pintype "passive"))
    )
    (net (code "21") (name "/DI1_1") (class "Default")
      (node (ref "P4") (pin "8") (pinfunction "8_8") (pintype "passive"))
      (node (ref "S4") (pin "1") (pinfunction "1_1") (pintype "passive"))
    )
    (net (code "22") (name "/DI2") (class "Default")
      (node (ref "OP1") (pin "4") (pinfunction "4_4") (pintype "passive"))
      (node (ref "P4") (pin "5") (pinfunction "5_5") (pintype "passive"))
      (node (ref "R24") (pin "2") (pinfunction "2_2") (pintype "passive"))
    )
    (net (code "23") (name "/DI2_2") (class "Default")
      (node (ref "P4") (pin "6") (pinfunction "6_6") (pintype "passive"))
      (node (ref "S1") (pin "1") (pinfunction "1_1") (pintype "passive"))
    )
    (net (code "24") (name "/DI3") (class "Default")
      (node (ref "OP1") (pin "6") (pinfunction "6_6") (pintype "passive"))
      (node (ref "P4") (pin "3") (pinfunction "3_3") (pintype "passive"))
      (node (ref "R25") (pin "2") (pinfunction "2_2") (pintype "passive"))
    )
    (net (code "25") (name "/DI3_3") (class "Default")
      (node (ref "P4") (pin "4") (pinfunction "4_4") (pintype "passive"))
      (node (ref "S2") (pin "1") (pinfunction "1_1") (pintype "passive"))
    )
    (net (code "26") (name "/DI4") (class "Default")
      (node (ref "OP1") (pin "8") (pinfunction "8_8") (pintype "passive"))
      (node (ref "P4") (pin "1") (pinfunction "1_1") (pintype "passive"))
      (node (ref "R26") (pin "2") (pinfunction "2_2") (pintype "passive"))
    )
    (net (code "27") (name "/DI4_4") (class "Default")
      (node (ref "P4") (pin "2") (pinfunction "2_2") (pintype "passive"))
      (node (ref "S3") (pin "1") (pinfunction "1_1") (pintype "passive"))
    )
    (net (code "28") (name "/Input1") (class "Default")
      (node (ref "OP1") (pin "16") (pinfunction "16_16") (pintype "passive"))
      (node (ref "R35") (pin "1") (pinfunction "1_1") (pintype "passive"))
      (node (ref "U8") (pin "19") (pinfunction "PC0(SCL)_19") (pintype "passive"))
    )
    (net (code "29") (name "/Input2") (class "Default")
      (node (ref "OP1") (pin "14") (pinfunction "14_14") (pintype "passive"))
      (node (ref "R32") (pin "1") (pinfunction "1_1") (pintype "passive"))
      (node (ref "U8") (pin "20") (pinfunction "PC1(SDA)_20") (pintype "passive"))
    )
    (net (code "30") (name "/Input3") (class "Default")
      (node (ref "OP1") (pin "12") (pinfunction "12_12") (pintype "passive"))
      (node (ref "R33") (pin "1") (pinfunction "1_1") (pintype "passive"))
      (node (ref "U8") (pin "25") (pinfunction "PC6(TOSC1)_25") (pintype "passive"))
    )
    (net (code "31") (name "/Input4") (class "Default")
      (node (ref "OP1") (pin "10") (pinfunction "10_10") (pintype "passive"))
      (node (ref "R34") (pin "1") (pinfunction "1_1") (pintype "passive"))
      (node (ref "U8") (pin "26") (pinfunction "PC7(TOSC2)_26") (pintype "passive"))
    )
    (net (code "32") (name "/MISO") (class "Default")
      (node (ref "P12") (pin "4") (pinfunction "4_4") (pintype "passive"))
      (node (ref "U8") (pin "2") (pinfunction "PB6(MISO)_2") (pintype "passive"))
    )
    (net (code "33") (name "/MOSI") (class "Default")
      (node (ref "P12") (pin "3") (pinfunction "3_3") (pintype "passive"))
      (node (ref "U8") (pin "1") (pinfunction "PB5(MOSI)_1") (pintype "passive"))
    )
    (net (code "34") (name "/NoUse1") (class "Default")
      (node (ref "D7") (pin "2") (pinfunction "2_2") (pintype "passive"))
      (node (ref "U8") (pin "12") (pinfunction "PD3(INT1)_12") (pintype "passive"))
    )
    (net (code "35") (name "/NoUse2") (class "Default")
      (node (ref "D8") (pin "2") (pinfunction "2_2") (pintype "passive"))
      (node (ref "U8") (pin "15") (pinfunction "PD6(ICP1)_15") (pintype "passive"))
    )
    (net (code "36") (name "/NoUse3") (class "Default")
      (node (ref "U8") (pin "32") (pinfunction "PA5(ADC5)_32") (pintype "passive"))
    )
    (net (code "37") (name "/NoUse4") (class "Default")
      (node (ref "U8") (pin "31") (pinfunction "PA6(ADC6)_31") (pintype "passive"))
    )
    (net (code "38") (name "/NoUse5") (class "Default")
      (node (ref "U8") (pin "30") (pinfunction "PA7(ADC7)_30") (pintype "passive"))
    )
    (net (code "39") (name "/Out1") (class "Default")
      (node (ref "R5") (pin "2") (pinfunction "2_2") (pintype "passive"))
      (node (ref "RL1") (pin "2") (pinfunction "2_2") (pintype "passive"))
      (node (ref "U1") (pin "16") (pinfunction "OUT1_16") (pintype "open_collector"))
    )
    (net (code "40") (name "/Out2") (class "Default")
      (node (ref "R6") (pin "2") (pinfunction "2_2") (pintype "passive"))
      (node (ref "RL2") (pin "2") (pinfunction "2_2") (pintype "passive"))
      (node (ref "U1") (pin "15") (pinfunction "OUT2_15") (pintype "open_collector"))
    )
    (net (code "41") (name "/Out3") (class "Default")
      (node (ref "R7") (pin "2") (pinfunction "2_2") (pintype "passive"))
      (node (ref "RL3") (pin "2") (pinfunction "2_2") (pintype "passive"))
      (node (ref "U1") (pin "14") (pinfunction "OUT3_14") (pintype "open_collector"))
    )
    (net (code "42") (name "/Out4") (class "Default")
      (node (ref "U1") (pin "13") (pinfunction "OUT4_13") (pintype "open_collector"))
    )
    (net (code "43") (name "/Output1") (class "Default")
      (node (ref "U1") (pin "1") (pinfunction "IN1_1") (pintype "input"))
      (node (ref "U8") (pin "40") (pinfunction "PB0(XCK/T0)_40") (pintype "passive"))
    )
    (net (code "44") (name "/Output2") (class "Default")
      (node (ref "U1") (pin "2") (pinfunction "IN2_2") (pintype "input"))
      (node (ref "U8") (pin "41") (pinfunction "PB1(T1)_41") (pintype "passive"))
    )
    (net (code "45") (name "/Output3") (class "Default")
      (node (ref "U1") (pin "3") (pinfunction "IN3_3") (pintype "input"))
      (node (ref "U8") (pin "42") (pinfunction "PB2(AIN0/INT12)_42") (pintype "passive"))
    )
    (net (code "46") (name "/Output4") (class "Default")
      (node (ref "U1") (pin "4") (pinfunction "IN4_4") (pintype "input"))
      (node (ref "U8") (pin "44") (pinfunction "PB4(~{SS})_44") (pintype "passive"))
    )
    (net (code "47") (name "/PWM1") (class "Default")
      (node (ref "R3") (pin "2") (pinfunction "2_2") (pintype "passive"))
      (node (ref "U8") (pin "16") (pinfunction "PD7(OC2)_16") (pintype "passive"))
    )
    (net (code "48") (name "/PWM2") (class "Default")
      (node (ref "R4") (pin "2") (pinfunction "2_2") (pintype "passive"))
      (node (ref "U8") (pin "14") (pinfunction "PD5(OC1A)_14") (pintype "passive"))
    )
    (net (code "49") (name "/PWM3") (class "Default")
      (node (ref "R1") (pin "2") (pinfunction "2_2") (pintype "passive"))
      (node (ref "U8") (pin "13") (pinfunction "PD4(OC1B)_13") (pintype "passive"))
    )
    (net (code "50") (name "/PWM4") (class "Default")
      (node (ref "R2") (pin "2") (pinfunction "2_2") (pintype "passive"))
      (node (ref "U8") (pin "43") (pinfunction "PB3(AIN1/OC0)_43") (pintype "passive"))
    )
    (net (code "51") (name "/RXD") (class "Default")
      (node (ref "U8") (pin "9") (pinfunction "PD0(RXD)_9") (pintype "passive"))
      (node (ref "U9") (pin "1") (pinfunction "RO_1") (pintype "passive"))
    )
    (net (code "52") (name "/Reset") (class "Default")
      (node (ref "P12") (pin "6") (pinfunction "6_6") (pintype "passive"))
      (node (ref "R59") (pin "1") (pinfunction "1_1") (pintype "passive"))
      (node (ref "U8") (pin "4") (pinfunction "~{RESET}_4") (pintype "passive"))
    )
    (net (code "53") (name "/R{slash}TXD") (class "Default")
      (node (ref "D4") (pin "1") (pinfunction "1_1") (pintype "passive"))
      (node (ref "U8") (pin "11") (pinfunction "PD2(INT0)_11") (pintype "passive"))
      (node (ref "U9") (pin "2") (pinfunction "RE_2") (pintype "passive"))
      (node (ref "U9") (pin "3") (pinfunction "DE_3") (pintype "passive"))
    )
    (net (code "54") (name "/SCK") (class "Default")
      (node (ref "P12") (pin "5") (pinfunction "5_5") (pintype "passive"))
      (node (ref "U8") (pin "3") (pinfunction "PB7(SCK)_3") (pintype "passive"))
    )
    (net (code "55") (name "/TCK") (class "Default")
      (node (ref "P11") (pin "6") (pinfunction "6_6") (pintype "passive"))
      (node (ref "U8") (pin "21") (pinfunction "PC2(TCK)_21") (pintype "passive"))
    )
    (net (code "56") (name "/TDI") (class "Default")
      (node (ref "P11") (pin "3") (pinfunction "3_3") (pintype "passive"))
      (node (ref "U8") (pin "24") (pinfunction "PC5(TDI)_24") (pintype "passive"))
    )
    (net (code "57") (name "/TDO") (class "Default")
      (node (ref "P11") (pin "4") (pinfunction "4_4") (pintype "passive"))
      (node (ref "U8") (pin "23") (pinfunction "PC4(TDO)_23") (pintype "passive"))
    )
    (net (code "58") (name "/TMS") (class "Default")
      (node (ref "P11") (pin "5") (pinfunction "5_5") (pintype "passive"))
      (node (ref "U8") (pin "22") (pinfunction "PC3(TMS)_22") (pintype "passive"))
    )
    (net (code "59") (name "/TXD") (class "Default")
      (node (ref "U8") (pin "10") (pinfunction "PD1(TXD)_10") (pintype "passive"))
      (node (ref "U9") (pin "4") (pinfunction "DI_4") (pintype "passive"))
    )
    (net (code "60") (name "/XTAL1") (class "Default")
      (node (ref "C28") (pin "1") (pinfunction "1_1") (pintype "passive"))
      (node (ref "U8") (pin "8") (pinfunction "XTAL1_8") (pintype "passive"))
      (node (ref "Y1") (pin "1") (pinfunction "OSC1_1") (pintype "passive"))
    )
    (net (code "61") (name "/XTAL2") (class "Default")
      (node (ref "C27") (pin "1") (pinfunction "1_1") (pintype "passive"))
      (node (ref "U8") (pin "7") (pinfunction "XTAL2_7") (pintype "passive"))
      (node (ref "Y1") (pin "2") (pinfunction "OSC2_2") (pintype "passive"))
    )
    (net (code "62") (name "/模块选择") (class "Default")
      (node (ref "C38") (pin "1") (pinfunction "1_1") (pintype "passive"))
      (node (ref "R66") (pin "1") (pinfunction "1_1") (pintype "passive"))
      (node (ref "R67") (pin "2") (pinfunction "2_2") (pintype "passive"))
      (node (ref "U8") (pin "33") (pinfunction "PA4(ADC4)_33") (pintype "passive"))
    )
    (net (code "63") (name "5V") (class "Default")
      (node (ref "C30") (pin "2") (pinfunction "2_2") (pintype "passive"))
      (node (ref "C32") (pin "2") (pinfunction "2_2") (pintype "passive"))
      (node (ref "C34") (pin "2") (pinfunction "2_2") (pintype "passive"))
      (node (ref "C35") (pin "1") (pinfunction "1_1") (pintype "passive"))
      (node (ref "C36") (pin "1") (pinfunction "1_1") (pintype "passive"))
      (node (ref "C37") (pin "1") (pinfunction "1_1") (pintype "passive"))
      (node (ref "P11") (pin "8") (pinfunction "8_8") (pintype "passive"))
      (node (ref "P12") (pin "7") (pinfunction "7_7") (pintype "passive"))
      (node (ref "P13") (pin "3") (pinfunction "3_3") (pintype "passive"))
      (node (ref "P13") (pin "4") (pinfunction "4_4") (pintype "passive"))
      (node (ref "P14") (pin "3") (pinfunction "3_3") (pintype "passive"))
      (node (ref "P14") (pin "4") (pinfunction "4_4") (pintype "passive"))
      (node (ref "P8") (pin "1") (pinfunction "1_1") (pintype "passive"))
      (node (ref "P8") (pin "2") (pinfunction "2_2") (pintype "passive"))
      (node (ref "P8") (pin "3") (pinfunction "3_3") (pintype "passive"))
      (node (ref "R100") (pin "1") (pinfunction "1_1") (pintype "passive"))
      (node (ref "R101") (pin "1") (pinfunction "1_1") (pintype "passive"))
      (node (ref "R32") (pin "2") (pinfunction "0_2") (pintype "passive"))
      (node (ref "R33") (pin "2") (pinfunction "0_2") (pintype "passive"))
      (node (ref "R34") (pin "2") (pinfunction "0_2") (pintype "passive"))
      (node (ref "R35") (pin "2") (pinfunction "0_2") (pintype "passive"))
      (node (ref "R59") (pin "2") (pinfunction "2_2") (pintype "passive"))
      (node (ref "R66") (pin "2") (pinfunction "2_2") (pintype "passive"))
      (node (ref "R69") (pin "2") (pinfunction "2_2") (pintype "passive"))
      (node (ref "U8") (pin "17") (pinfunction "VCC_17") (pintype "passive"))
      (node (ref "U8") (pin "27") (pinfunction "AVCC_27") (pintype "passive"))
      (node (ref "U8") (pin "38") (pinfunction "VCC_38") (pintype "passive"))
      (node (ref "U8") (pin "5") (pinfunction "VCC_5") (pintype "passive"))
      (node (ref "U9") (pin "8") (pinfunction "VCC_8") (pintype "passive"))
    )
    (net (code "64") (name "12V") (class "Default")
      (node (ref "C13") (pin "2") (pinfunction "2_2") (pintype "passive"))
      (node (ref "C14") (pin "2") (pinfunction "2_2") (pintype "passive"))
      (node (ref "C15") (pin "1") (pinfunction "1_1") (pintype "passive"))
      (node (ref "C16") (pin "1") (pinfunction "1_1") (pintype "passive"))
      (node (ref "D1") (pin "1") (pinfunction "A_1") (pintype "passive"))
      (node (ref "D2") (pin "1") (pinfunction "A_1") (pintype "passive"))
      (node (ref "D3") (pin "1") (pinfunction "A_1") (pintype "passive"))
      (node (ref "P13") (pin "1") (pinfunction "1_1") (pintype "passive"))
      (node (ref "P13") (pin "2") (pinfunction "2_2") (pintype "passive"))
      (node (ref "P14") (pin "1") (pinfunction "1_1") (pintype "passive"))
      (node (ref "P14") (pin "2") (pinfunction "2_2") (pintype "passive"))
      (node (ref "R40") (pin "2") (pinfunction "2_2") (pintype "passive"))
      (node (ref "R41") (pin "2") (pinfunction "2_2") (pintype "passive"))
      (node (ref "R42") (pin "2") (pinfunction "2_2") (pintype "passive"))
      (node (ref "R43") (pin "2") (pinfunction "2_2") (pintype "passive"))
      (node (ref "R44") (pin "2") (pinfunction "2_2") (pintype "passive"))
      (node (ref "R45") (pin "2") (pinfunction "2_2") (pintype "passive"))
      (node (ref "R46") (pin "2") (pinfunction "2_2") (pintype "passive"))
      (node (ref "R47") (pin "2") (pinfunction "2_2") (pintype "passive"))
      (node (ref "RL1") (pin "1") (pinfunction "1_1") (pintype "passive"))
      (node (ref "RL2") (pin "1") (pinfunction "1_1") (pintype "passive"))
      (node (ref "RL3") (pin "1") (pinfunction "1_1") (pintype "passive"))
      (node (ref "S1") (pin "6") (pinfunction "6_6") (pintype "passive"))
      (node (ref "S2") (pin "6") (pinfunction "6_6") (pintype "passive"))
      (node (ref "S3") (pin "6") (pinfunction "6_6") (pintype "passive"))
      (node (ref "S4") (pin "6") (pinfunction "6_6") (pintype "passive"))
      (node (ref "U1") (pin "9") (pinfunction "COM_9") (pintype "passive"))
      (node (ref "U2") (pin "8") (pinfunction "V_8") (pintype "passive"))
      (node (ref "U3") (pin "8") (pinfunction "V_8") (pintype "passive"))
      (node (ref "U4") (pin "8") (pinfunction "V_8") (pintype "passive"))
      (node (ref "U5") (pin "8") (pinfunction "V_8") (pintype "passive"))
      (node (ref "U6") (pin "8") (pinfunction "V_8") (pintype "passive"))
      (node (ref "U7") (pin "8") (pinfunction "V_8") (pintype "passive"))
    )
    (net (code "65") (name "DO1") (class "Default")
      (node (ref "P1") (pin "2") (pinfunction "2_2") (pintype "passive"))
      (node (ref "RL1") (pin "3") (pinfunction "3_3") (pintype "passive"))
    )
    (net (code "66") (name "DO1_1") (class "Default")
      (node (ref "P1") (pin "1") (pinfunction "1_1") (pintype "passive"))
      (node (ref "RL1") (pin "4") (pinfunction "4_4") (pintype "passive"))
    )
    (net (code "67") (name "DO2") (class "Default")
      (node (ref "P2") (pin "2") (pinfunction "2_2") (pintype "passive"))
      (node (ref "RL2") (pin "3") (pinfunction "3_3") (pintype "passive"))
    )
    (net (code "68") (name "DO2_2") (class "Default")
      (node (ref "P2") (pin "1") (pinfunction "1_1") (pintype "passive"))
      (node (ref "RL2") (pin "4") (pinfunction "4_4") (pintype "passive"))
    )
    (net (code "69") (name "DO3") (class "Default")
      (node (ref "P3") (pin "2") (pinfunction "2_2") (pintype "passive"))
      (node (ref "RL3") (pin "3") (pinfunction "3_3") (pintype "passive"))
    )
    (net (code "70") (name "DO3_3") (class "Default")
      (node (ref "P3") (pin "1") (pinfunction "1_1") (pintype "passive"))
      (node (ref "RL3") (pin "4") (pinfunction "4_4") (pintype "passive"))
    )
    (net (code "71") (name "GND") (class "Default")
      (node (ref "C1") (pin "2") (pinfunction "2_2") (pintype "passive"))
      (node (ref "C13") (pin "1") (pinfunction "1_1") (pintype "passive"))
      (node (ref "C14") (pin "1") (pinfunction "1_1") (pintype "passive"))
      (node (ref "C15") (pin "2") (pinfunction "2_2") (pintype "passive"))
      (node (ref "C16") (pin "2") (pinfunction "2_2") (pintype "passive"))
      (node (ref "C17") (pin "2") (pinfunction "2_2") (pintype "passive"))
      (node (ref "C18") (pin "2") (pinfunction "2_2") (pintype "passive"))
      (node (ref "C19") (pin "2") (pinfunction "2_2") (pintype "passive"))
      (node (ref "C2") (pin "2") (pinfunction "2_2") (pintype "passive"))
      (node (ref "C20") (pin "2") (pinfunction "2_2") (pintype "passive"))
      (node (ref "C21") (pin "2") (pinfunction "2_2") (pintype "passive"))
      (node (ref "C22") (pin "2") (pinfunction "2_2") (pintype "passive"))
      (node (ref "C23") (pin "2") (pinfunction "2_2") (pintype "passive"))
      (node (ref "C24") (pin "2") (pinfunction "2_2") (pintype "passive"))
      (node (ref "C25") (pin "2") (pinfunction "2_2") (pintype "passive"))
      (node (ref "C26") (pin "2") (pinfunction "2_2") (pintype "passive"))
      (node (ref "C28") (pin "2") (pinfunction "2_2") (pintype "passive"))
      (node (ref "C29") (pin "1") (pinfunction "1_1") (pintype "passive"))
      (node (ref "C3") (pin "1") (pinfunction "1_1") (pintype "passive"))
      (node (ref "C30") (pin "1") (pinfunction "1_1") (pintype "passive"))
      (node (ref "C31") (pin "2") (pinfunction "2_2") (pintype "passive"))
      (node (ref "C32") (pin "1") (pinfunction "1_1") (pintype "passive"))
      (node (ref "C33") (pin "2") (pinfunction "2_2") (pintype "passive"))
      (node (ref "C34") (pin "1") (pinfunction "1_1") (pintype "passive"))
      (node (ref "C35") (pin "2") (pinfunction "2_2") (pintype "passive"))
      (node (ref "C36") (pin "2") (pinfunction "2_2") (pintype "passive"))
      (node (ref "C37") (pin "2") (pinfunction "2_2") (pintype "passive"))
      (node (ref "C38") (pin "2") (pinfunction "2_2") (pintype "passive"))
      (node (ref "C4") (pin "1") (pinfunction "1_1") (pintype "passive"))
      (node (ref "C5") (pin "2") (pinfunction "2_2") (pintype "passive"))
      (node (ref "C6") (pin "2") (pinfunction "2_2") (pintype "passive"))
      (node (ref "C7") (pin "1") (pinfunction "1_1") (pintype "passive"))
      (node (ref "C8") (pin "1") (pinfunction "1_1") (pintype "passive"))
      (node (ref "D5") (pin "A") (pinfunction "A_A") (pintype "passive"))
      (node (ref "D6") (pin "A") (pinfunction "A_A") (pintype "passive"))
      (node (ref "DW1") (pin "A") (pinfunction "A_A") (pintype "passive"))
      (node (ref "DW2") (pin "A") (pinfunction "A_A") (pintype "passive"))
      (node (ref "DW3") (pin "A") (pinfunction "A_A") (pintype "passive"))
      (node (ref "DW4") (pin "A") (pinfunction "A_A") (pintype "passive"))
      (node (ref "OP1") (pin "11") (pinfunction "11_11") (pintype "passive"))
      (node (ref "OP1") (pin "13") (pinfunction "13_13") (pintype "passive"))
      (node (ref "OP1") (pin "15") (pinfunction "15_15") (pintype "passive"))
      (node (ref "OP1") (pin "9") (pinfunction "9_9") (pintype "passive"))
      (node (ref "P11") (pin "1") (pinfunction "1_1") (pintype "passive"))
      (node (ref "P12") (pin "1") (pinfunction "1_1") (pintype "passive"))
      (node (ref "P13") (pin "5") (pinfunction "5_5") (pintype "passive"))
      (node (ref "P13") (pin "6") (pinfunction "6_6") (pintype "passive"))
      (node (ref "P14") (pin "5") (pinfunction "5_5") (pintype "passive"))
      (node (ref "P14") (pin "6") (pinfunction "6_6") (pintype "passive"))
      (node (ref "P5") (pin "2") (pinfunction "2_2") (pintype "passive"))
      (node (ref "P5") (pin "4") (pinfunction "4_4") (pintype "passive"))
      (node (ref "P5") (pin "6") (pinfunction "6_6") (pintype "passive"))
      (node (ref "P5") (pin "8") (pinfunction "8_8") (pintype "passive"))
      (node (ref "P6") (pin "2") (pinfunction "2_2") (pintype "passive"))
      (node (ref "P6") (pin "4") (pinfunction "4_4") (pintype "passive"))
      (node (ref "P6") (pin "6") (pinfunction "6_6") (pintype "passive"))
      (node (ref "P6") (pin "8") (pinfunction "8_8") (pintype "passive"))
      (node (ref "P9") (pin "1") (pinfunction "1_1") (pintype "passive"))
      (node (ref "P9") (pin "2") (pinfunction "2_2") (pintype "passive"))
      (node (ref "P9") (pin "3") (pinfunction "3_3") (pintype "passive"))
      (node (ref "R12") (pin "2") (pinfunction "2_2") (pintype "passive"))
      (node (ref "R13") (pin "2") (pinfunction "2_2") (pintype "passive"))
      (node (ref "R14") (pin "2") (pinfunction "2_2") (pintype "passive"))
      (node (ref "R15") (pin "2") (pinfunction "2_2") (pintype "passive"))
      (node (ref "R48") (pin "1") (pinfunction "1_1") (pintype "passive"))
      (node (ref "R49") (pin "1") (pinfunction "1_1") (pintype "passive"))
      (node (ref "R50") (pin "1") (pinfunction "1_1") (pintype "passive"))
      (node (ref "R51") (pin "1") (pinfunction "1_1") (pintype "passive"))
      (node (ref "R54") (pin "2") (pinfunction "2_2") (pintype "passive"))
      (node (ref "R55") (pin "2") (pinfunction "2_2") (pintype "passive"))
      (node (ref "R56") (pin "2") (pinfunction "2_2") (pintype "passive"))
      (node (ref "R57") (pin "2") (pinfunction "2_2") (pintype "passive"))
      (node (ref "R58") (pin "2") (pinfunction "2_2") (pintype "passive"))
      (node (ref "R62") (pin "2") (pinfunction "2_2") (pintype "passive"))
      (node (ref "R63") (pin "2") (pinfunction "2_2") (pintype "passive"))
      (node (ref "R64") (pin "2") (pinfunction "2_2") (pintype "passive"))
      (node (ref "R65") (pin "2") (pinfunction "2_2") (pintype "passive"))
      (node (ref "R67") (pin "1") (pinfunction "1_1") (pintype "passive"))
      (node (ref "R68") (pin "1") (pinfunction "1_1") (pintype "passive"))
      (node (ref "R71") (pin "1") (pinfunction "1_1") (pintype "passive"))
      (node (ref "S1") (pin "3") (pinfunction "3_3") (pintype "passive"))
      (node (ref "S2") (pin "3") (pinfunction "3_3") (pintype "passive"))
      (node (ref "S3") (pin "3") (pinfunction "3_3") (pintype "passive"))
      (node (ref "S4") (pin "3") (pinfunction "3_3") (pintype "passive"))
      (node (ref "U1") (pin "8") (pinfunction "GND_8") (pintype "power_in"))
      (node (ref "U4") (pin "4") (pinfunction "G_4") (pintype "passive"))
      (node (ref "U5") (pin "4") (pinfunction "G_4") (pintype "passive"))
      (node (ref "U6") (pin "4") (pinfunction "G_4") (pintype "passive"))
      (node (ref "U7") (pin "4") (pinfunction "G_4") (pintype "passive"))
      (node (ref "U8") (pin "18") (pinfunction "GND_18") (pintype "passive"))
      (node (ref "U8") (pin "28") (pinfunction "GND_28") (pintype "passive"))
      (node (ref "U8") (pin "39") (pinfunction "GND_39") (pintype "passive"))
      (node (ref "U8") (pin "6") (pinfunction "GND_6") (pintype "passive"))
      (node (ref "U9") (pin "5") (pinfunction "GND_5") (pintype "passive"))
    )
    (net (code "72") (name "Net-(C1-Pad1)") (class "Default")
      (node (ref "C1") (pin "1") (pinfunction "1_1") (pintype "passive"))
      (node (ref "R2") (pin "1") (pinfunction "1_1") (pintype "passive"))
      (node (ref "R9") (pin "2") (pinfunction "2_2") (pintype "passive"))
    )
    (net (code "73") (name "Net-(C2-Pad1)") (class "Default")
      (node (ref "C2") (pin "1") (pinfunction "1_1") (pintype "passive"))
      (node (ref "R11") (pin "2") (pinfunction "2_2") (pintype "passive"))
      (node (ref "R4") (pin "1") (pinfunction "1_1") (pintype "passive"))
    )
    (net (code "74") (name "Net-(C3-Pad2)") (class "Default")
      (node (ref "C3") (pin "2") (pinfunction "2_2") (pintype "passive"))
      (node (ref "R1") (pin "1") (pinfunction "1_1") (pintype "passive"))
      (node (ref "R8") (pin "2") (pinfunction "2_2") (pintype "passive"))
    )
    (net (code "75") (name "Net-(C4-Pad2)") (class "Default")
      (node (ref "C4") (pin "2") (pinfunction "2_2") (pintype "passive"))
      (node (ref "R10") (pin "2") (pinfunction "2_2") (pintype "passive"))
      (node (ref "R3") (pin "1") (pinfunction "1_1") (pintype "passive"))
    )
    (net (code "76") (name "Net-(C27-Pad2)") (class "Default")
      (node (ref "C27") (pin "2") (pinfunction "2_2") (pintype "passive"))
      (node (ref "R58") (pin "1") (pinfunction "1_1") (pintype "passive"))
    )
    (net (code "77") (name "Net-(D1-K)") (class "Default")
      (node (ref "D1") (pin "2") (pinfunction "K_2") (pintype "passive"))
      (node (ref "R5") (pin "1") (pinfunction "1_1") (pintype "passive"))
    )
    (net (code "78") (name "Net-(D2-K)") (class "Default")
      (node (ref "D2") (pin "2") (pinfunction "K_2") (pintype "passive"))
      (node (ref "R6") (pin "1") (pinfunction "1_1") (pintype "passive"))
    )
    (net (code "79") (name "Net-(D3-K)") (class "Default")
      (node (ref "D3") (pin "2") (pinfunction "K_2") (pintype "passive"))
      (node (ref "R7") (pin "1") (pinfunction "1_1") (pintype "passive"))
    )
    (net (code "80") (name "Net-(D7-Pad1)") (class "Default")
      (node (ref "D7") (pin "1") (pinfunction "1_1") (pintype "passive"))
      (node (ref "R100") (pin "2") (pinfunction "2_2") (pintype "passive"))
    )
    (net (code "81") (name "Net-(D8-Pad1)") (class "Default")
      (node (ref "D8") (pin "1") (pinfunction "1_1") (pintype "passive"))
      (node (ref "R101") (pin "2") (pinfunction "2_2") (pintype "passive"))
    )
    (net (code "82") (name "Net-(F1-Pad2)") (class "Default")
      (node (ref "F1") (pin "2") (pinfunction "2_2") (pintype "passive"))
      (node (ref "S9") (pin "1") (pinfunction "1_1") (pintype "passive"))
    )
    (net (code "83") (name "Net-(F2-Pad2)") (class "Default")
      (node (ref "F2") (pin "2") (pinfunction "2_2") (pintype "passive"))
      (node (ref "S10") (pin "1") (pinfunction "1_1") (pintype "passive"))
    )
    (net (code "84") (name "Net-(F3-Pad2)") (class "Default")
      (node (ref "F3") (pin "2") (pinfunction "2_2") (pintype "passive"))
      (node (ref "S11") (pin "1") (pinfunction "1_1") (pintype "passive"))
    )
    (net (code "85") (name "Net-(F4-Pad2)") (class "Default")
      (node (ref "F4") (pin "2") (pinfunction "2_2") (pintype "passive"))
      (node (ref "S12") (pin "1") (pinfunction "1_1") (pintype "passive"))
    )
    (net (code "86") (name "Net-(OP1-Pad1)") (class "Default")
      (node (ref "OP1") (pin "1") (pinfunction "1_1") (pintype "passive"))
      (node (ref "R31") (pin "2") (pinfunction "2_2") (pintype "passive"))
    )
    (net (code "87") (name "Net-(OP1-Pad3)") (class "Default")
      (node (ref "OP1") (pin "3") (pinfunction "3_3") (pintype "passive"))
      (node (ref "R28") (pin "2") (pinfunction "2_2") (pintype "passive"))
    )
    (net (code "88") (name "Net-(OP1-Pad5)") (class "Default")
      (node (ref "OP1") (pin "5") (pinfunction "5_5") (pintype "passive"))
      (node (ref "R29") (pin "2") (pinfunction "2_2") (pintype "passive"))
    )
    (net (code "89") (name "Net-(OP1-Pad7)") (class "Default")
      (node (ref "OP1") (pin "7") (pinfunction "7_7") (pintype "passive"))
      (node (ref "R30") (pin "2") (pinfunction "2_2") (pintype "passive"))
    )
    (net (code "90") (name "Net-(Q1-B)") (class "Default")
      (node (ref "Q1") (pin "2") (pinfunction "B_2") (pintype "passive"))
      (node (ref "U4") (pin "1") (pinfunction "OUT_1") (pintype "passive"))
    )
    (net (code "91") (name "Net-(Q1-C)") (class "Default")
      (node (ref "Q1") (pin "1") (pinfunction "C_1") (pintype "passive"))
      (node (ref "R40") (pin "1") (pinfunction "1_1") (pintype "passive"))
      (node (ref "U4") (pin "5") (pinfunction "+_5") (pintype "passive"))
    )
    (net (code "92") (name "Net-(Q1-E)") (class "Default")
      (node (ref "Q1") (pin "3") (pinfunction "E_3") (pintype "passive"))
      (node (ref "R50") (pin "2") (pinfunction "2_2") (pintype "passive"))
      (node (ref "U4") (pin "2") (pinfunction "--_2") (pintype "passive"))
    )
    (net (code "93") (name "Net-(Q2-B)") (class "Default")
      (node (ref "Q2") (pin "2") (pinfunction "B_2") (pintype "passive"))
      (node (ref "U5") (pin "1") (pinfunction "OUT_1") (pintype "passive"))
    )
    (net (code "94") (name "Net-(Q2-C)") (class "Default")
      (node (ref "Q2") (pin "1") (pinfunction "C_1") (pintype "passive"))
      (node (ref "R41") (pin "1") (pinfunction "1_1") (pintype "passive"))
      (node (ref "U5") (pin "5") (pinfunction "+_5") (pintype "passive"))
    )
    (net (code "95") (name "Net-(Q2-E)") (class "Default")
      (node (ref "Q2") (pin "3") (pinfunction "E_3") (pintype "passive"))
      (node (ref "R48") (pin "2") (pinfunction "2_2") (pintype "passive"))
      (node (ref "U5") (pin "2") (pinfunction "--_2") (pintype "passive"))
    )
    (net (code "96") (name "Net-(Q3-B)") (class "Default")
      (node (ref "Q3") (pin "2") (pinfunction "B_2") (pintype "passive"))
      (node (ref "U6") (pin "1") (pinfunction "OUT_1") (pintype "passive"))
    )
    (net (code "97") (name "Net-(Q3-C)") (class "Default")
      (node (ref "Q3") (pin "1") (pinfunction "C_1") (pintype "passive"))
      (node (ref "R42") (pin "1") (pinfunction "1_1") (pintype "passive"))
      (node (ref "U6") (pin "5") (pinfunction "+_5") (pintype "passive"))
    )
    (net (code "98") (name "Net-(Q3-E)") (class "Default")
      (node (ref "Q3") (pin "3") (pinfunction "E_3") (pintype "passive"))
      (node (ref "R49") (pin "2") (pinfunction "2_2") (pintype "passive"))
      (node (ref "U6") (pin "2") (pinfunction "--_2") (pintype "passive"))
    )
    (net (code "99") (name "Net-(Q4-B)") (class "Default")
      (node (ref "Q4") (pin "2") (pinfunction "B_2") (pintype "passive"))
      (node (ref "U7") (pin "1") (pinfunction "OUT_1") (pintype "passive"))
    )
    (net (code "100") (name "Net-(Q4-C)") (class "Default")
      (node (ref "Q4") (pin "1") (pinfunction "C_1") (pintype "passive"))
      (node (ref "R46") (pin "1") (pinfunction "1_1") (pintype "passive"))
      (node (ref "U7") (pin "5") (pinfunction "+_5") (pintype "passive"))
    )
    (net (code "101") (name "Net-(Q4-E)") (class "Default")
      (node (ref "Q4") (pin "3") (pinfunction "E_3") (pintype "passive"))
      (node (ref "R51") (pin "2") (pinfunction "2_2") (pintype "passive"))
      (node (ref "U7") (pin "2") (pinfunction "--_2") (pintype "passive"))
    )
    (net (code "102") (name "Net-(Q5-B)") (class "Default")
      (node (ref "Q5") (pin "2") (pinfunction "B_2") (pintype "passive"))
      (node (ref "U4") (pin "7") (pinfunction "OUT_7") (pintype "passive"))
    )
    (net (code "103") (name "Net-(Q5-E)") (class "Default")
      (node (ref "Q5") (pin "3") (pinfunction "E_3") (pintype "passive"))
      (node (ref "R43") (pin "1") (pinfunction "1_1") (pintype "passive"))
      (node (ref "U4") (pin "6") (pinfunction "--_6") (pintype "passive"))
    )
    (net (code "104") (name "Net-(Q6-B)") (class "Default")
      (node (ref "Q6") (pin "2") (pinfunction "B_2") (pintype "passive"))
      (node (ref "U5") (pin "7") (pinfunction "OUT_7") (pintype "passive"))
    )
    (net (code "105") (name "Net-(Q6-E)") (class "Default")
      (node (ref "Q6") (pin "3") (pinfunction "E_3") (pintype "passive"))
      (node (ref "R44") (pin "1") (pinfunction "1_1") (pintype "passive"))
      (node (ref "U5") (pin "6") (pinfunction "--_6") (pintype "passive"))
    )
    (net (code "106") (name "Net-(Q7-B)") (class "Default")
      (node (ref "Q7") (pin "2") (pinfunction "B_2") (pintype "passive"))
      (node (ref "U6") (pin "7") (pinfunction "OUT_7") (pintype "passive"))
    )
    (net (code "107") (name "Net-(Q7-E)") (class "Default")
      (node (ref "Q7") (pin "3") (pinfunction "E_3") (pintype "passive"))
      (node (ref "R45") (pin "1") (pinfunction "1_1") (pintype "passive"))
      (node (ref "U6") (pin "6") (pinfunction "--_6") (pintype "passive"))
    )
    (net (code "108") (name "Net-(Q8-B)") (class "Default")
      (node (ref "Q8") (pin "2") (pinfunction "B_2") (pintype "passive"))
      (node (ref "U7") (pin "7") (pinfunction "OUT_7") (pintype "passive"))
    )
    (net (code "109") (name "Net-(Q8-E)") (class "Default")
      (node (ref "Q8") (pin "3") (pinfunction "E_3") (pintype "passive"))
      (node (ref "R47") (pin "1") (pinfunction "1_1") (pintype "passive"))
      (node (ref "U7") (pin "6") (pinfunction "--_6") (pintype "passive"))
    )
    (net (code "110") (name "Net-(R24-Pad1)") (class "Default")
      (node (ref "R24") (pin "1") (pinfunction "1_1") (pintype "passive"))
      (node (ref "R28") (pin "1") (pinfunction "1_1") (pintype "passive"))
      (node (ref "S1") (pin "4") (pinfunction "4_4") (pintype "passive"))
    )
    (net (code "111") (name "Net-(R25-Pad1)") (class "Default")
      (node (ref "R25") (pin "1") (pinfunction "1_1") (pintype "passive"))
      (node (ref "R29") (pin "1") (pinfunction "1_1") (pintype "passive"))
      (node (ref "S2") (pin "4") (pinfunction "4_4") (pintype "passive"))
    )
    (net (code "112") (name "Net-(R26-Pad1)") (class "Default")
      (node (ref "R26") (pin "1") (pinfunction "1_1") (pintype "passive"))
      (node (ref "R30") (pin "1") (pinfunction "1_1") (pintype "passive"))
      (node (ref "S3") (pin "4") (pinfunction "4_4") (pintype "passive"))
    )
    (net (code "113") (name "Net-(R27-Pad1)") (class "Default")
      (node (ref "R27") (pin "1") (pinfunction "1_1") (pintype "passive"))
      (node (ref "R31") (pin "1") (pinfunction "1_1") (pintype "passive"))
      (node (ref "S4") (pin "4") (pinfunction "4_4") (pintype "passive"))
    )
    (net (code "114") (name "Net-(R52-Pad1)") (class "Default")
      (node (ref "R52") (pin "1") (pinfunction "1_1") (pintype "passive"))
      (node (ref "S9") (pin "2") (pinfunction "2_2") (pintype "passive"))
    )
    (net (code "115") (name "Net-(R52-Pad2)") (class "Default")
      (node (ref "R52") (pin "2") (pinfunction "2_2") (pintype "passive"))
      (node (ref "R54") (pin "1") (pinfunction "1_1") (pintype "passive"))
      (node (ref "S9") (pin "5") (pinfunction "5_5") (pintype "passive"))
    )
    (net (code "116") (name "Net-(R53-Pad1)") (class "Default")
      (node (ref "R53") (pin "1") (pinfunction "1_1") (pintype "passive"))
      (node (ref "S10") (pin "2") (pinfunction "2_2") (pintype "passive"))
    )
    (net (code "117") (name "Net-(R53-Pad2)") (class "Default")
      (node (ref "R53") (pin "2") (pinfunction "2_2") (pintype "passive"))
      (node (ref "R56") (pin "1") (pinfunction "1_1") (pintype "passive"))
      (node (ref "S10") (pin "5") (pinfunction "5_5") (pintype "passive"))
    )
    (net (code "118") (name "Net-(R55-Pad1)") (class "Default")
      (node (ref "R55") (pin "1") (pinfunction "1_1") (pintype "passive"))
      (node (ref "S9") (pin "3") (pinfunction "3_3") (pintype "passive"))
      (node (ref "S9") (pin "6") (pinfunction "6_6") (pintype "passive"))
    )
    (net (code "119") (name "Net-(R57-Pad1)") (class "Default")
      (node (ref "R57") (pin "1") (pinfunction "1_1") (pintype "passive"))
      (node (ref "S10") (pin "3") (pinfunction "3_3") (pintype "passive"))
      (node (ref "S10") (pin "6") (pinfunction "6_6") (pintype "passive"))
    )
    (net (code "120") (name "Net-(R60-Pad1)") (class "Default")
      (node (ref "R60") (pin "1") (pinfunction "1_1") (pintype "passive"))
      (node (ref "S11") (pin "2") (pinfunction "2_2") (pintype "passive"))
    )
    (net (code "121") (name "Net-(R60-Pad2)") (class "Default")
      (node (ref "R60") (pin "2") (pinfunction "2_2") (pintype "passive"))
      (node (ref "R62") (pin "1") (pinfunction "1_1") (pintype "passive"))
      (node (ref "S11") (pin "5") (pinfunction "5_5") (pintype "passive"))
    )
    (net (code "122") (name "Net-(R61-Pad1)") (class "Default")
      (node (ref "R61") (pin "1") (pinfunction "1_1") (pintype "passive"))
      (node (ref "S12") (pin "2") (pinfunction "2_2") (pintype "passive"))
    )
    (net (code "123") (name "Net-(R61-Pad2)") (class "Default")
      (node (ref "R61") (pin "2") (pinfunction "2_2") (pintype "passive"))
      (node (ref "R64") (pin "1") (pinfunction "1_1") (pintype "passive"))
      (node (ref "S12") (pin "5") (pinfunction "5_5") (pintype "passive"))
    )
    (net (code "124") (name "Net-(R63-Pad1)") (class "Default")
      (node (ref "R63") (pin "1") (pinfunction "1_1") (pintype "passive"))
      (node (ref "S11") (pin "3") (pinfunction "3_3") (pintype "passive"))
      (node (ref "S11") (pin "6") (pinfunction "6_6") (pintype "passive"))
    )
    (net (code "125") (name "Net-(R65-Pad1)") (class "Default")
      (node (ref "R65") (pin "1") (pinfunction "1_1") (pintype "passive"))
      (node (ref "S12") (pin "3") (pinfunction "3_3") (pintype "passive"))
      (node (ref "S12") (pin "6") (pinfunction "6_6") (pintype "passive"))
    )
    (net (code "126") (name "Net-(R68-0)") (class "Default")
      (node (ref "D4") (pin "2") (pinfunction "2_2") (pintype "passive"))
      (node (ref "R68") (pin "2") (pinfunction "0_2") (pintype "passive"))
    )
    (net (code "127") (name "Net-(S1-Pad2)") (class "Default")
      (node (ref "S1") (pin "2") (pinfunction "2_2") (pintype "passive"))
      (node (ref "S1") (pin "5") (pinfunction "5_5") (pintype "passive"))
    )
    (net (code "128") (name "Net-(S2-Pad2)") (class "Default")
      (node (ref "S2") (pin "2") (pinfunction "2_2") (pintype "passive"))
      (node (ref "S2") (pin "5") (pinfunction "5_5") (pintype "passive"))
    )
    (net (code "129") (name "Net-(S3-Pad2)") (class "Default")
      (node (ref "S3") (pin "2") (pinfunction "2_2") (pintype "passive"))
      (node (ref "S3") (pin "5") (pinfunction "5_5") (pintype "passive"))
    )
    (net (code "130") (name "Net-(S4-Pad2)") (class "Default")
      (node (ref "S4") (pin "2") (pinfunction "2_2") (pintype "passive"))
      (node (ref "S4") (pin "5") (pinfunction "5_5") (pintype "passive"))
    )
    (net (code "131") (name "Net-(U2A-+)") (class "Default")
      (node (ref "C7") (pin "2") (pinfunction "2_2") (pintype "passive"))
      (node (ref "R8") (pin "1") (pinfunction "1_1") (pintype "passive"))
      (node (ref "U2") (pin "3") (pinfunction "+_3") (pintype "passive"))
    )
    (net (code "132") (name "Net-(U2A---)") (class "Default")
      (node (ref "C9") (pin "1") (pinfunction "1_1") (pintype "passive"))
      (node (ref "R12") (pin "1") (pinfunction "1_1") (pintype "passive"))
      (node (ref "R16") (pin "2") (pinfunction "2_2") (pintype "passive"))
      (node (ref "U2") (pin "2") (pinfunction "--_2") (pintype "passive"))
    )
    (net (code "133") (name "Net-(U2A-OUT)") (class "Default")
      (node (ref "R20") (pin "2") (pinfunction "2_2") (pintype "passive"))
      (node (ref "U2") (pin "1") (pinfunction "OUT_1") (pintype "passive"))
    )
    (net (code "134") (name "Net-(U2B-+)") (class "Default")
      (node (ref "C5") (pin "1") (pinfunction "1_1") (pintype "passive"))
      (node (ref "R9") (pin "1") (pinfunction "1_1") (pintype "passive"))
      (node (ref "U2") (pin "5") (pinfunction "+_5") (pintype "passive"))
    )
    (net (code "135") (name "Net-(U2B---)") (class "Default")
      (node (ref "C10") (pin "1") (pinfunction "1_1") (pintype "passive"))
      (node (ref "R13") (pin "1") (pinfunction "1_1") (pintype "passive"))
      (node (ref "R18") (pin "2") (pinfunction "2_2") (pintype "passive"))
      (node (ref "U2") (pin "6") (pinfunction "--_6") (pintype "passive"))
    )
    (net (code "136") (name "Net-(U2B-OUT)") (class "Default")
      (node (ref "R21") (pin "2") (pinfunction "2_2") (pintype "passive"))
      (node (ref "U2") (pin "7") (pinfunction "OUT_7") (pintype "passive"))
    )
    (net (code "137") (name "Net-(U3A-+)") (class "Default")
      (node (ref "C8") (pin "2") (pinfunction "2_2") (pintype "passive"))
      (node (ref "R10") (pin "1") (pinfunction "1_1") (pintype "passive"))
      (node (ref "U3") (pin "3") (pinfunction "+_3") (pintype "passive"))
    )
    (net (code "138") (name "Net-(U3A---)") (class "Default")
      (node (ref "C11") (pin "1") (pinfunction "1_1") (pintype "passive"))
      (node (ref "R14") (pin "1") (pinfunction "1_1") (pintype "passive"))
      (node (ref "R17") (pin "2") (pinfunction "2_2") (pintype "passive"))
      (node (ref "U3") (pin "2") (pinfunction "--_2") (pintype "passive"))
    )
    (net (code "139") (name "Net-(U3A-OUT)") (class "Default")
      (node (ref "R22") (pin "2") (pinfunction "2_2") (pintype "passive"))
      (node (ref "U3") (pin "1") (pinfunction "OUT_1") (pintype "passive"))
    )
    (net (code "140") (name "Net-(U3B-+)") (class "Default")
      (node (ref "C6") (pin "1") (pinfunction "1_1") (pintype "passive"))
      (node (ref "R11") (pin "1") (pinfunction "1_1") (pintype "passive"))
      (node (ref "U3") (pin "5") (pinfunction "+_5") (pintype "passive"))
    )
    (net (code "141") (name "Net-(U3B---)") (class "Default")
      (node (ref "C12") (pin "1") (pinfunction "1_1") (pintype "passive"))
      (node (ref "R15") (pin "1") (pinfunction "1_1") (pintype "passive"))
      (node (ref "R19") (pin "2") (pinfunction "2_2") (pintype "passive"))
      (node (ref "U3") (pin "6") (pinfunction "--_6") (pintype "passive"))
    )
    (net (code "142") (name "Net-(U3B-OUT)") (class "Default")
      (node (ref "R23") (pin "2") (pinfunction "2_2") (pintype "passive"))
      (node (ref "U3") (pin "7") (pinfunction "OUT_7") (pintype "passive"))
    )
    (net (code "143") (name "Net-(U4A-+)") (class "Default")
      (node (ref "R36") (pin "1") (pinfunction "1_1") (pintype "passive"))
      (node (ref "U4") (pin "3") (pinfunction "+_3") (pintype "passive"))
    )
    (net (code "144") (name "Net-(U5A-+)") (class "Default")
      (node (ref "R37") (pin "1") (pinfunction "1_1") (pintype "passive"))
      (node (ref "U5") (pin "3") (pinfunction "+_3") (pintype "passive"))
    )
    (net (code "145") (name "Net-(U6A-+)") (class "Default")
      (node (ref "R38") (pin "1") (pinfunction "1_1") (pintype "passive"))
      (node (ref "U6") (pin "3") (pinfunction "+_3") (pintype "passive"))
    )
    (net (code "146") (name "Net-(U7A-+)") (class "Default")
      (node (ref "R39") (pin "1") (pinfunction "1_1") (pintype "passive"))
      (node (ref "U7") (pin "3") (pinfunction "+_3") (pintype "passive"))
    )
    (net (code "147") (name "Net-(U9-A)") (class "Default")
      (node (ref "D6") (pin "K") (pinfunction "K_K") (pintype "passive"))
      (node (ref "F6") (pin "2") (pinfunction "2_2") (pintype "passive"))
      (node (ref "R69") (pin "1") (pinfunction "1_1") (pintype "passive"))
      (node (ref "R70") (pin "1") (pinfunction "1_1") (pintype "passive"))
      (node (ref "U9") (pin "6") (pinfunction "A_6") (pintype "passive"))
    )
    (net (code "148") (name "Net-(U9-B)") (class "Default")
      (node (ref "D5") (pin "K") (pinfunction "K_K") (pintype "passive"))
      (node (ref "F5") (pin "2") (pinfunction "2_2") (pintype "passive"))
      (node (ref "R70") (pin "2") (pinfunction "2_2") (pintype "passive"))
      (node (ref "R71") (pin "2") (pinfunction "2_2") (pintype "passive"))
      (node (ref "U9") (pin "7") (pinfunction "B_7") (pintype "passive"))
    )
    (net (code "149") (name "mAout1") (class "Default")
      (node (ref "Q5") (pin "1") (pinfunction "C_1") (pintype "passive"))
      (node (ref "S6") (pin "2") (pinfunction "2_2") (pintype "passive"))
      (node (ref "S6") (pin "5") (pinfunction "5_5") (pintype "passive"))
    )
    (net (code "150") (name "mAout2") (class "Default")
      (node (ref "Q8") (pin "1") (pinfunction "C_1") (pintype "passive"))
      (node (ref "S7") (pin "2") (pinfunction "2_2") (pintype "passive"))
      (node (ref "S7") (pin "5") (pinfunction "5_5") (pintype "passive"))
    )
    (net (code "151") (name "mAout3") (class "Default")
      (node (ref "Q6") (pin "1") (pinfunction "C_1") (pintype "passive"))
      (node (ref "S8") (pin "2") (pinfunction "2_2") (pintype "passive"))
      (node (ref "S8") (pin "5") (pinfunction "5_5") (pintype "passive"))
    )
    (net (code "152") (name "mAout4") (class "Default")
      (node (ref "Q7") (pin "1") (pinfunction "C_1") (pintype "passive"))
      (node (ref "S5") (pin "2") (pinfunction "2_2") (pintype "passive"))
      (node (ref "S5") (pin "5") (pinfunction "5_5") (pintype "passive"))
    )
    (net (code "153") (name "unconnected-(P11-Pad2)") (class "Default")
      (node (ref "P11") (pin "2") (pinfunction "2_2") (pintype "passive"))
    )
    (net (code "154") (name "unconnected-(P11-Pad7)") (class "Default")
      (node (ref "P11") (pin "7") (pinfunction "7_7") (pintype "passive"))
    )
    (net (code "155") (name "unconnected-(P11-Pad9)") (class "Default")
      (node (ref "P11") (pin "9") (pinfunction "9_9") (pintype "passive"))
    )
    (net (code "156") (name "unconnected-(P11-Pad10)") (class "Default")
      (node (ref "P11") (pin "10") (pinfunction "10_10") (pintype "passive"))
    )
    (net (code "157") (name "unconnected-(P12-Pad2)") (class "Default")
      (node (ref "P12") (pin "2") (pinfunction "2_2") (pintype "passive"))
    )
    (net (code "158") (name "unconnected-(P12-Pad8)") (class "Default")
      (node (ref "P12") (pin "8") (pinfunction "8_8") (pintype "passive"))
    )
    (net (code "159") (name "unconnected-(P12-Pad9)") (class "Default")
      (node (ref "P12") (pin "9") (pinfunction "9_9") (pintype "passive"))
    )
    (net (code "160") (name "unconnected-(P12-Pad10)") (class "Default")
      (node (ref "P12") (pin "10") (pinfunction "10_10") (pintype "passive"))
    )
    (net (code "161") (name "unconnected-(P13-Pad9)") (class "Default")
      (node (ref "P13") (pin "9") (pinfunction "9_9") (pintype "passive"))
    )
    (net (code "162") (name "unconnected-(P13-Pad10)") (class "Default")
      (node (ref "P13") (pin "10") (pinfunction "10_10") (pintype "passive"))
    )
    (net (code "163") (name "unconnected-(P14-Pad9)") (class "Default")
      (node (ref "P14") (pin "9") (pinfunction "9_9") (pintype "passive"))
    )
    (net (code "164") (name "unconnected-(P14-Pad10)") (class "Default")
      (node (ref "P14") (pin "10") (pinfunction "10_10") (pintype "passive"))
    )
    (net (code "165") (name "unconnected-(U1-IN5-Pad5)") (class "Default")
      (node (ref "U1") (pin "5") (pinfunction "IN5_5") (pintype "input+no_connect"))
    )
    (net (code "166") (name "unconnected-(U1-IN6-Pad6)") (class "Default")
      (node (ref "U1") (pin "6") (pinfunction "IN6_6") (pintype "input+no_connect"))
    )
    (net (code "167") (name "unconnected-(U1-IN7-Pad7)") (class "Default")
      (node (ref "U1") (pin "7") (pinfunction "IN7_7") (pintype "input+no_connect"))
    )
    (net (code "168") (name "unconnected-(U1-OUT5-Pad12)") (class "Default")
      (node (ref "U1") (pin "12") (pinfunction "OUT5_12") (pintype "open_collector+no_connect"))
    )
    (net (code "169") (name "unconnected-(U1-OUT6-Pad11)") (class "Default")
      (node (ref "U1") (pin "11") (pinfunction "OUT6_11") (pintype "open_collector+no_connect"))
    )
    (net (code "170") (name "unconnected-(U1-OUT7-Pad10)") (class "Default")
      (node (ref "U1") (pin "10") (pinfunction "OUT7_10") (pintype "open_collector+no_connect"))
    )
    (net (code "171") (name "unconnected-(U2A-G-Pad4)") (class "Default")
      (node (ref "U2") (pin "4") (pinfunction "G_4") (pintype "passive"))
    )
    (net (code "172") (name "unconnected-(U3A-G-Pad4)") (class "Default")
      (node (ref "U3") (pin "4") (pinfunction "G_4") (pintype "passive"))
    )
  )
)
